# v2.net
KiCad netlist of a schematic drawn in EAGLE
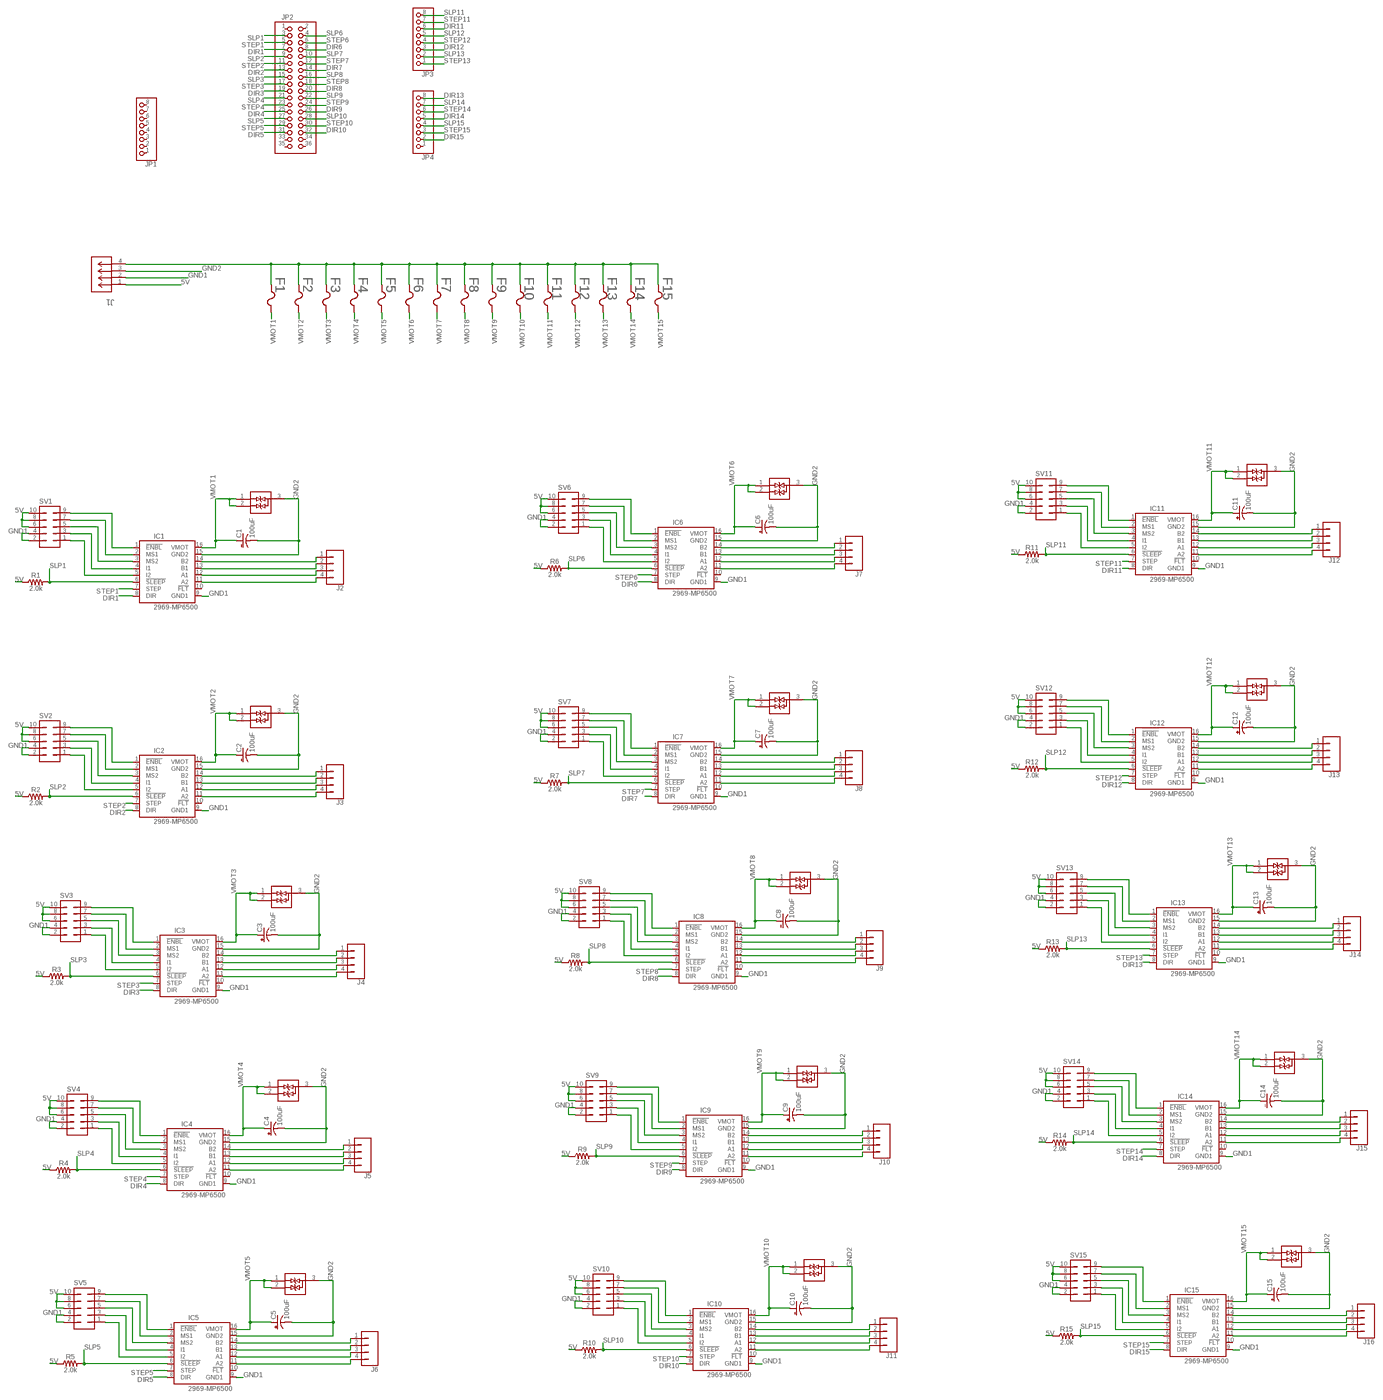
[diagram p0: schematic, sheet 1, overview]
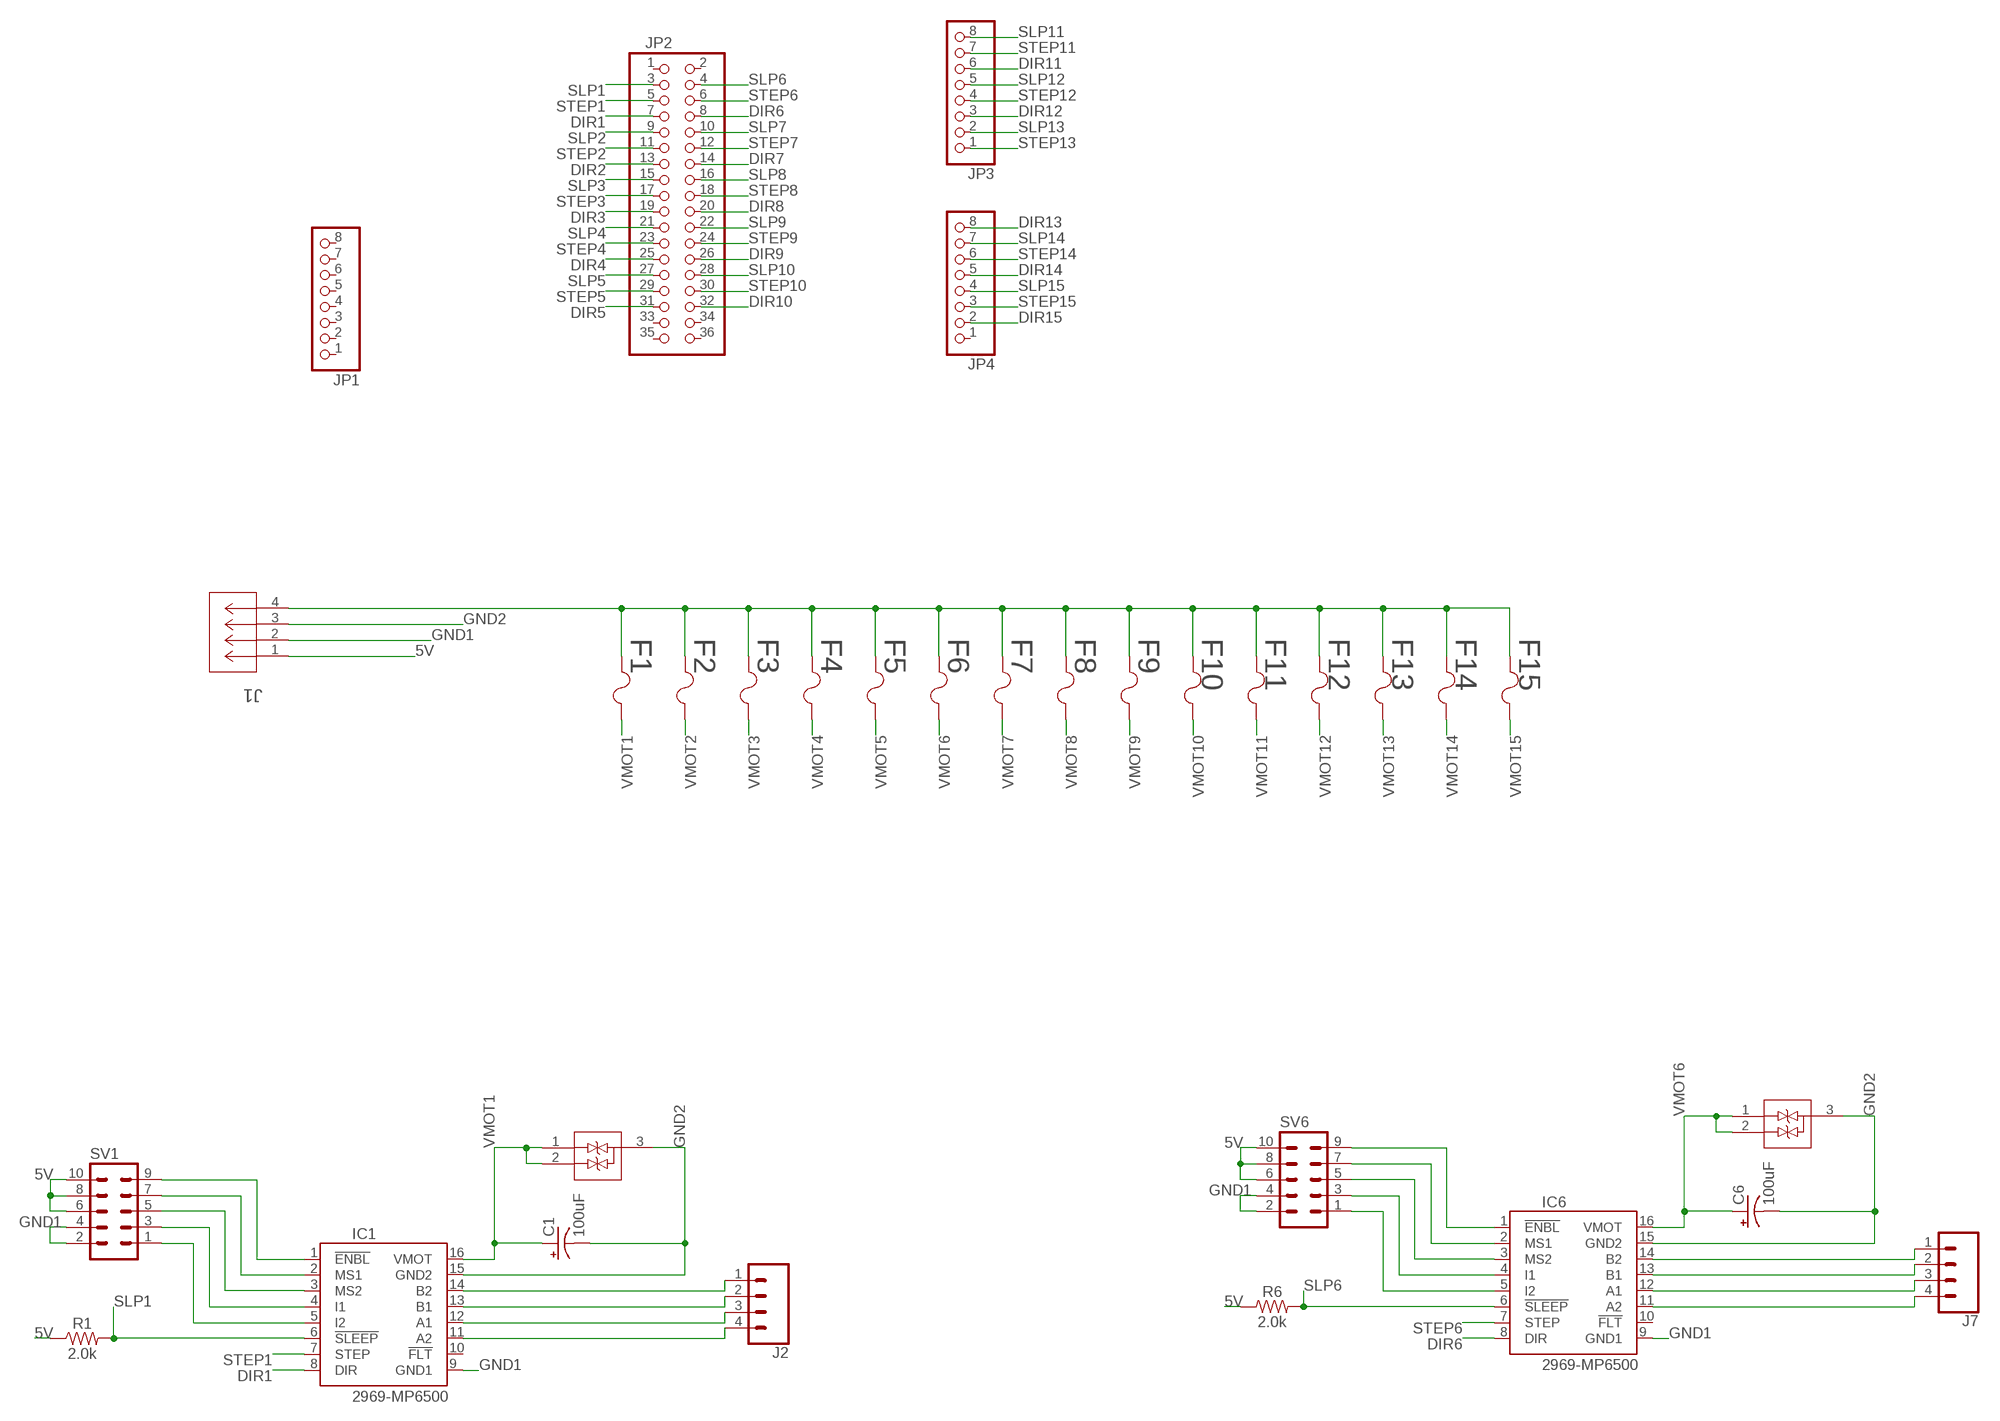
[diagram p1: schematic, sheet 1, part 1 of 4]
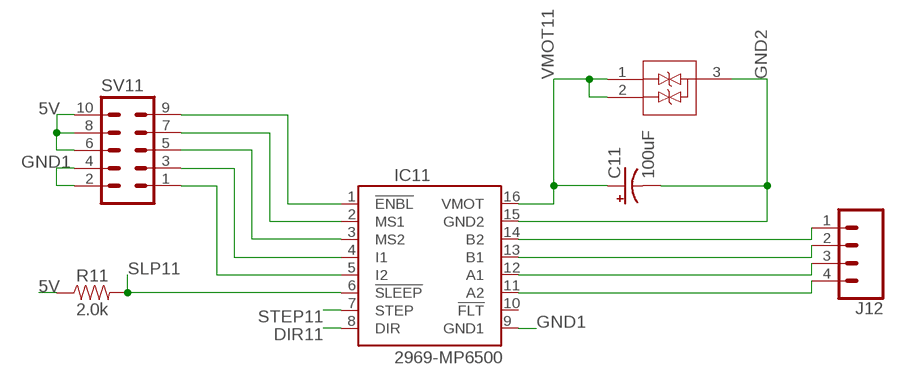
[diagram p2: schematic, sheet 1, part 2 of 4]
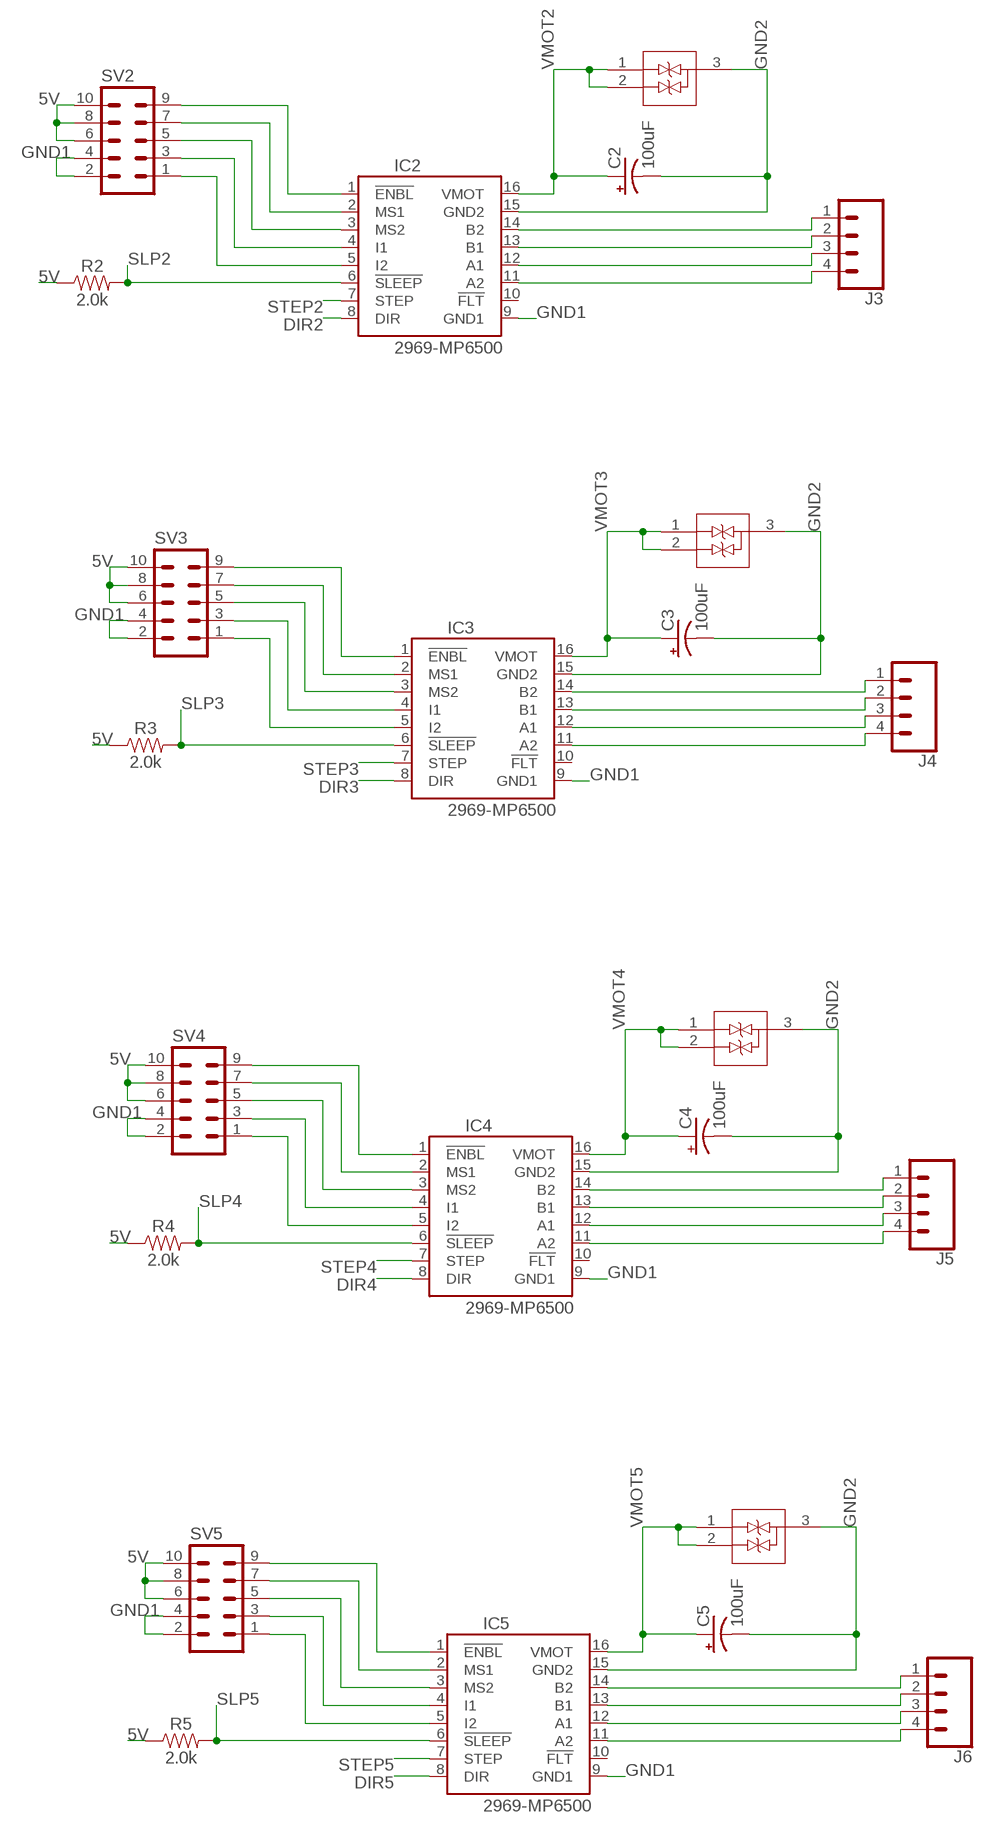
[diagram p3: schematic, sheet 1, part 3 of 4]
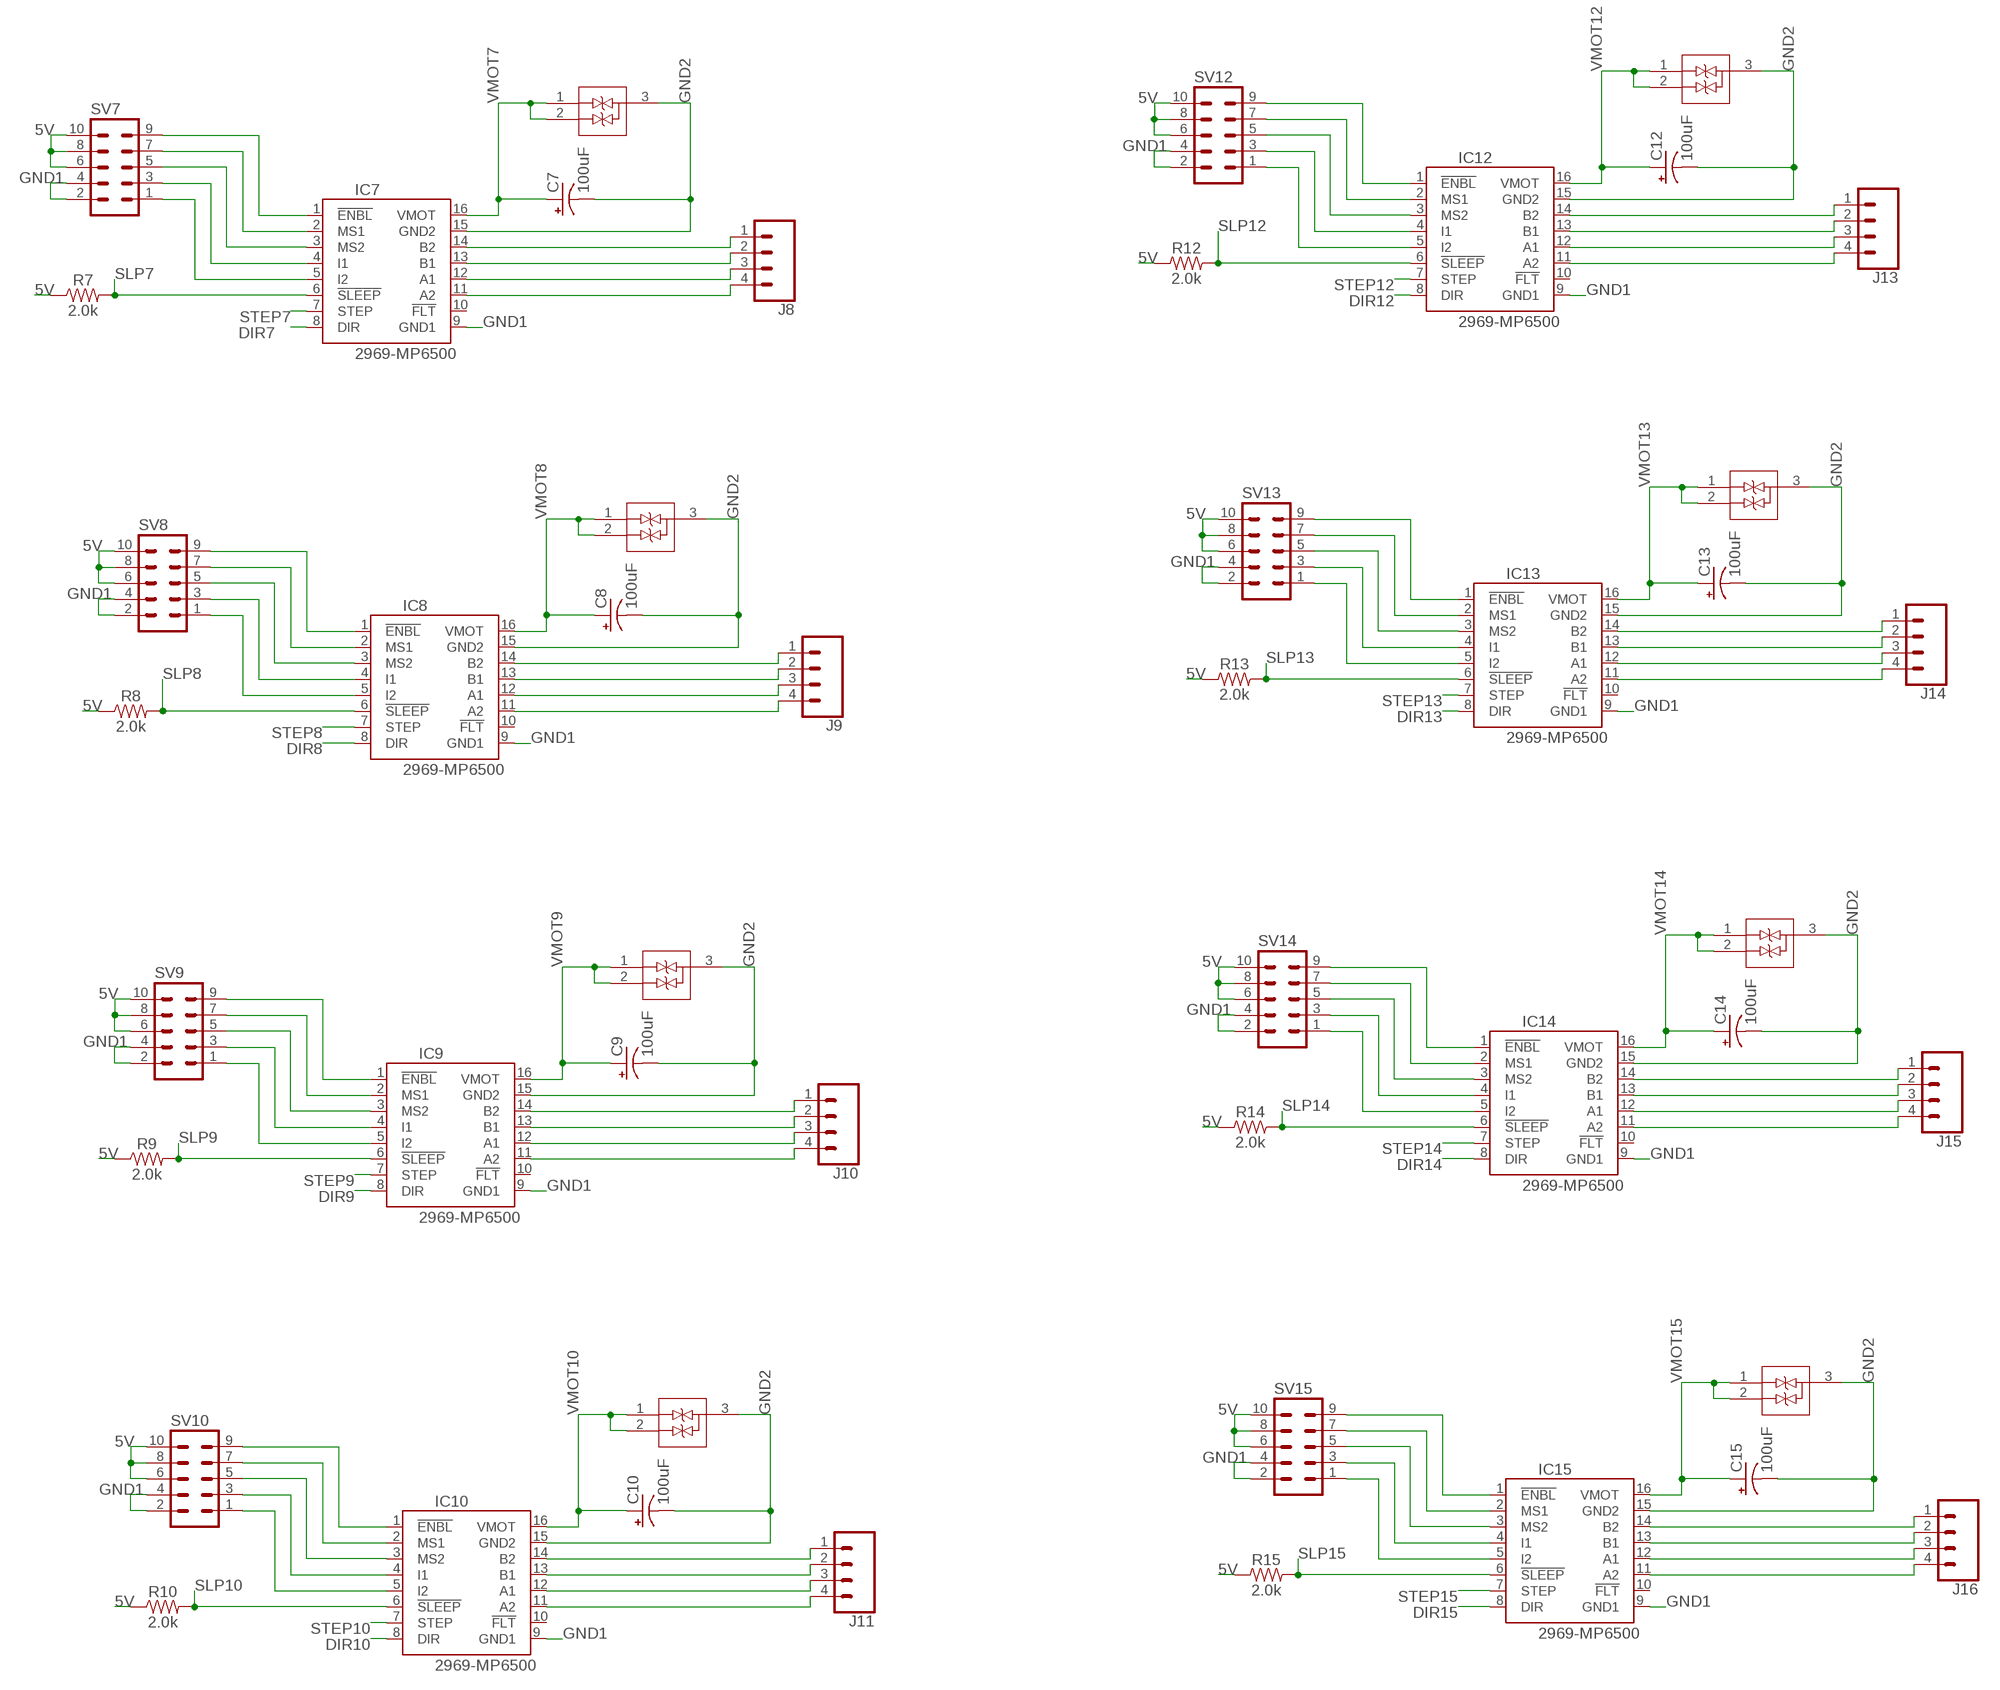
[diagram p4: schematic, sheet 1, part 4 of 4]

(export (version "E")
  (design (tool "Eeschema 10.0.6"))
  (components
    (comp (ref "C1")
      (value "100uF")
      (footprint "eagle-import:8X10.5")
      (libsource (lib "eagle-import") (part "100UF-POLAR-8X10.5-50V"))
    )
    (comp (ref "C2")
      (value "100uF")
      (footprint "eagle-import:8X10.5")
      (libsource (lib "eagle-import") (part "100UF-POLAR-8X10.5-50V"))
    )
    (comp (ref "C3")
      (value "100uF")
      (footprint "eagle-import:8X10.5")
      (libsource (lib "eagle-import") (part "100UF-POLAR-8X10.5-50V"))
    )
    (comp (ref "C4")
      (value "100uF")
      (footprint "eagle-import:8X10.5")
      (libsource (lib "eagle-import") (part "100UF-POLAR-8X10.5-50V"))
    )
    (comp (ref "C5")
      (value "100uF")
      (footprint "eagle-import:8X10.5")
      (libsource (lib "eagle-import") (part "100UF-POLAR-8X10.5-50V"))
    )
    (comp (ref "C6")
      (value "100uF")
      (footprint "eagle-import:8X10.5")
      (libsource (lib "eagle-import") (part "100UF-POLAR-8X10.5-50V"))
    )
    (comp (ref "C7")
      (value "100uF")
      (footprint "eagle-import:8X10.5")
      (libsource (lib "eagle-import") (part "100UF-POLAR-8X10.5-50V"))
    )
    (comp (ref "C8")
      (value "100uF")
      (footprint "eagle-import:8X10.5")
      (libsource (lib "eagle-import") (part "100UF-POLAR-8X10.5-50V"))
    )
    (comp (ref "C9")
      (value "100uF")
      (footprint "eagle-import:8X10.5")
      (libsource (lib "eagle-import") (part "100UF-POLAR-8X10.5-50V"))
    )
    (comp (ref "C10")
      (value "100uF")
      (footprint "eagle-import:8X10.5")
      (libsource (lib "eagle-import") (part "100UF-POLAR-8X10.5-50V"))
    )
    (comp (ref "C11")
      (value "100uF")
      (footprint "eagle-import:8X10.5")
      (libsource (lib "eagle-import") (part "100UF-POLAR-8X10.5-50V"))
    )
    (comp (ref "C12")
      (value "100uF")
      (footprint "eagle-import:8X10.5")
      (libsource (lib "eagle-import") (part "100UF-POLAR-8X10.5-50V"))
    )
    (comp (ref "C13")
      (value "100uF")
      (footprint "eagle-import:8X10.5")
      (libsource (lib "eagle-import") (part "100UF-POLAR-8X10.5-50V"))
    )
    (comp (ref "C14")
      (value "100uF")
      (footprint "eagle-import:8X10.5")
      (libsource (lib "eagle-import") (part "100UF-POLAR-8X10.5-50V"))
    )
    (comp (ref "C15")
      (value "100uF")
      (footprint "eagle-import:8X10.5")
      (libsource (lib "eagle-import") (part "100UF-POLAR-8X10.5-50V"))
    )
    (comp (ref "CR1")
      (value "PESD2CAN24DBZRQ1")
      (footprint "eagle-import:SOT-23_DBZ_TEX")
      (fields (field (name "COPYRIGHT") "Copyright (C) 2023 Ultra Librarian. All rights reserved."))
      (libsource (lib "eagle-import") (part "PESD2CAN24DBZRQ1"))
    )
    (comp (ref "CR2")
      (value "PESD2CAN24DBZRQ1")
      (footprint "eagle-import:SOT-23_DBZ_TEX")
      (fields (field (name "COPYRIGHT") "Copyright (C) 2023 Ultra Librarian. All rights reserved."))
      (libsource (lib "eagle-import") (part "PESD2CAN24DBZRQ1"))
    )
    (comp (ref "CR3")
      (value "PESD2CAN24DBZRQ1")
      (footprint "eagle-import:SOT-23_DBZ_TEX")
      (fields (field (name "COPYRIGHT") "Copyright (C) 2023 Ultra Librarian. All rights reserved."))
      (libsource (lib "eagle-import") (part "PESD2CAN24DBZRQ1"))
    )
    (comp (ref "CR4")
      (value "PESD2CAN24DBZRQ1")
      (footprint "eagle-import:SOT-23_DBZ_TEX")
      (fields (field (name "COPYRIGHT") "Copyright (C) 2023 Ultra Librarian. All rights reserved."))
      (libsource (lib "eagle-import") (part "PESD2CAN24DBZRQ1"))
    )
    (comp (ref "CR5")
      (value "PESD2CAN24DBZRQ1")
      (footprint "eagle-import:SOT-23_DBZ_TEX")
      (fields (field (name "COPYRIGHT") "Copyright (C) 2023 Ultra Librarian. All rights reserved."))
      (libsource (lib "eagle-import") (part "PESD2CAN24DBZRQ1"))
    )
    (comp (ref "CR6")
      (value "PESD2CAN24DBZRQ1")
      (footprint "eagle-import:SOT-23_DBZ_TEX")
      (fields (field (name "COPYRIGHT") "Copyright (C) 2023 Ultra Librarian. All rights reserved."))
      (libsource (lib "eagle-import") (part "PESD2CAN24DBZRQ1"))
    )
    (comp (ref "CR7")
      (value "PESD2CAN24DBZRQ1")
      (footprint "eagle-import:SOT-23_DBZ_TEX")
      (fields (field (name "COPYRIGHT") "Copyright (C) 2023 Ultra Librarian. All rights reserved."))
      (libsource (lib "eagle-import") (part "PESD2CAN24DBZRQ1"))
    )
    (comp (ref "CR8")
      (value "PESD2CAN24DBZRQ1")
      (footprint "eagle-import:SOT-23_DBZ_TEX")
      (fields (field (name "COPYRIGHT") "Copyright (C) 2023 Ultra Librarian. All rights reserved."))
      (libsource (lib "eagle-import") (part "PESD2CAN24DBZRQ1"))
    )
    (comp (ref "CR9")
      (value "PESD2CAN24DBZRQ1")
      (footprint "eagle-import:SOT-23_DBZ_TEX")
      (fields (field (name "COPYRIGHT") "Copyright (C) 2023 Ultra Librarian. All rights reserved."))
      (libsource (lib "eagle-import") (part "PESD2CAN24DBZRQ1"))
    )
    (comp (ref "CR10")
      (value "PESD2CAN24DBZRQ1")
      (footprint "eagle-import:SOT-23_DBZ_TEX")
      (fields (field (name "COPYRIGHT") "Copyright (C) 2023 Ultra Librarian. All rights reserved."))
      (libsource (lib "eagle-import") (part "PESD2CAN24DBZRQ1"))
    )
    (comp (ref "CR11")
      (value "PESD2CAN24DBZRQ1")
      (footprint "eagle-import:SOT-23_DBZ_TEX")
      (fields (field (name "COPYRIGHT") "Copyright (C) 2023 Ultra Librarian. All rights reserved."))
      (libsource (lib "eagle-import") (part "PESD2CAN24DBZRQ1"))
    )
    (comp (ref "CR12")
      (value "PESD2CAN24DBZRQ1")
      (footprint "eagle-import:SOT-23_DBZ_TEX")
      (fields (field (name "COPYRIGHT") "Copyright (C) 2023 Ultra Librarian. All rights reserved."))
      (libsource (lib "eagle-import") (part "PESD2CAN24DBZRQ1"))
    )
    (comp (ref "CR13")
      (value "PESD2CAN24DBZRQ1")
      (footprint "eagle-import:SOT-23_DBZ_TEX")
      (fields (field (name "COPYRIGHT") "Copyright (C) 2023 Ultra Librarian. All rights reserved."))
      (libsource (lib "eagle-import") (part "PESD2CAN24DBZRQ1"))
    )
    (comp (ref "CR14")
      (value "PESD2CAN24DBZRQ1")
      (footprint "eagle-import:SOT-23_DBZ_TEX")
      (fields (field (name "COPYRIGHT") "Copyright (C) 2023 Ultra Librarian. All rights reserved."))
      (libsource (lib "eagle-import") (part "PESD2CAN24DBZRQ1"))
    )
    (comp (ref "CR15")
      (value "PESD2CAN24DBZRQ1")
      (footprint "eagle-import:SOT-23_DBZ_TEX")
      (fields (field (name "COPYRIGHT") "Copyright (C) 2023 Ultra Librarian. All rights reserved."))
      (libsource (lib "eagle-import") (part "PESD2CAN24DBZRQ1"))
    )
    (comp (ref "F1")
      (value "0154003.DR")
      (footprint "eagle-import:0154SERIES_LTF")
      (fields (field (name "COPYRIGHT") "Copyright (C) 2023 Ultra Librarian. All rights reserved."))
      (libsource (lib "eagle-import") (part "0154003.DR"))
    )
    (comp (ref "F2")
      (value "0154003.DR")
      (footprint "eagle-import:0154SERIES_LTF")
      (fields (field (name "COPYRIGHT") "Copyright (C) 2023 Ultra Librarian. All rights reserved."))
      (libsource (lib "eagle-import") (part "0154003.DR"))
    )
    (comp (ref "F3")
      (value "0154003.DR")
      (footprint "eagle-import:0154SERIES_LTF")
      (fields (field (name "COPYRIGHT") "Copyright (C) 2023 Ultra Librarian. All rights reserved."))
      (libsource (lib "eagle-import") (part "0154003.DR"))
    )
    (comp (ref "F4")
      (value "0154003.DR")
      (footprint "eagle-import:0154SERIES_LTF")
      (fields (field (name "COPYRIGHT") "Copyright (C) 2023 Ultra Librarian. All rights reserved."))
      (libsource (lib "eagle-import") (part "0154003.DR"))
    )
    (comp (ref "F5")
      (value "0154003.DR")
      (footprint "eagle-import:0154SERIES_LTF")
      (fields (field (name "COPYRIGHT") "Copyright (C) 2023 Ultra Librarian. All rights reserved."))
      (libsource (lib "eagle-import") (part "0154003.DR"))
    )
    (comp (ref "F6")
      (value "0154003.DR")
      (footprint "eagle-import:0154SERIES_LTF")
      (fields (field (name "COPYRIGHT") "Copyright (C) 2023 Ultra Librarian. All rights reserved."))
      (libsource (lib "eagle-import") (part "0154003.DR"))
    )
    (comp (ref "F7")
      (value "0154003.DR")
      (footprint "eagle-import:0154SERIES_LTF")
      (fields (field (name "COPYRIGHT") "Copyright (C) 2023 Ultra Librarian. All rights reserved."))
      (libsource (lib "eagle-import") (part "0154003.DR"))
    )
    (comp (ref "F8")
      (value "0154003.DR")
      (footprint "eagle-import:0154SERIES_LTF")
      (fields (field (name "COPYRIGHT") "Copyright (C) 2023 Ultra Librarian. All rights reserved."))
      (libsource (lib "eagle-import") (part "0154003.DR"))
    )
    (comp (ref "F9")
      (value "0154003.DR")
      (footprint "eagle-import:0154SERIES_LTF")
      (fields (field (name "COPYRIGHT") "Copyright (C) 2023 Ultra Librarian. All rights reserved."))
      (libsource (lib "eagle-import") (part "0154003.DR"))
    )
    (comp (ref "F10")
      (value "0154003.DR")
      (footprint "eagle-import:0154SERIES_LTF")
      (fields (field (name "COPYRIGHT") "Copyright (C) 2023 Ultra Librarian. All rights reserved."))
      (libsource (lib "eagle-import") (part "0154003.DR"))
    )
    (comp (ref "F11")
      (value "0154003.DR")
      (footprint "eagle-import:0154SERIES_LTF")
      (fields (field (name "COPYRIGHT") "Copyright (C) 2023 Ultra Librarian. All rights reserved."))
      (libsource (lib "eagle-import") (part "0154003.DR"))
    )
    (comp (ref "F12")
      (value "0154003.DR")
      (footprint "eagle-import:0154SERIES_LTF")
      (fields (field (name "COPYRIGHT") "Copyright (C) 2023 Ultra Librarian. All rights reserved."))
      (libsource (lib "eagle-import") (part "0154003.DR"))
    )
    (comp (ref "F13")
      (value "0154003.DR")
      (footprint "eagle-import:0154SERIES_LTF")
      (fields (field (name "COPYRIGHT") "Copyright (C) 2023 Ultra Librarian. All rights reserved."))
      (libsource (lib "eagle-import") (part "0154003.DR"))
    )
    (comp (ref "F14")
      (value "0154003.DR")
      (footprint "eagle-import:0154SERIES_LTF")
      (fields (field (name "COPYRIGHT") "Copyright (C) 2023 Ultra Librarian. All rights reserved."))
      (libsource (lib "eagle-import") (part "0154003.DR"))
    )
    (comp (ref "F15")
      (value "0154003.DR")
      (footprint "eagle-import:0154SERIES_LTF")
      (fields (field (name "COPYRIGHT") "Copyright (C) 2023 Ultra Librarian. All rights reserved."))
      (libsource (lib "eagle-import") (part "0154003.DR"))
    )
    (comp (ref "IC1")
      (value "2969-MP6500")
      (footprint "eagle-import:MP6500")
      (libsource (lib "eagle-import") (part "2969-MP6500"))
    )
    (comp (ref "IC2")
      (value "2969-MP6500")
      (footprint "eagle-import:MP6500")
      (libsource (lib "eagle-import") (part "2969-MP6500"))
    )
    (comp (ref "IC3")
      (value "2969-MP6500")
      (footprint "eagle-import:MP6500")
      (libsource (lib "eagle-import") (part "2969-MP6500"))
    )
    (comp (ref "IC4")
      (value "2969-MP6500")
      (footprint "eagle-import:MP6500")
      (libsource (lib "eagle-import") (part "2969-MP6500"))
    )
    (comp (ref "IC5")
      (value "2969-MP6500")
      (footprint "eagle-import:MP6500")
      (libsource (lib "eagle-import") (part "2969-MP6500"))
    )
    (comp (ref "IC6")
      (value "2969-MP6500")
      (footprint "eagle-import:MP6500")
      (libsource (lib "eagle-import") (part "2969-MP6500"))
    )
    (comp (ref "IC7")
      (value "2969-MP6500")
      (footprint "eagle-import:MP6500")
      (libsource (lib "eagle-import") (part "2969-MP6500"))
    )
    (comp (ref "IC8")
      (value "2969-MP6500")
      (footprint "eagle-import:MP6500")
      (libsource (lib "eagle-import") (part "2969-MP6500"))
    )
    (comp (ref "IC9")
      (value "2969-MP6500")
      (footprint "eagle-import:MP6500")
      (libsource (lib "eagle-import") (part "2969-MP6500"))
    )
    (comp (ref "IC10")
      (value "2969-MP6500")
      (footprint "eagle-import:MP6500")
      (libsource (lib "eagle-import") (part "2969-MP6500"))
    )
    (comp (ref "IC11")
      (value "2969-MP6500")
      (footprint "eagle-import:MP6500")
      (libsource (lib "eagle-import") (part "2969-MP6500"))
    )
    (comp (ref "IC12")
      (value "2969-MP6500")
      (footprint "eagle-import:MP6500")
      (libsource (lib "eagle-import") (part "2969-MP6500"))
    )
    (comp (ref "IC13")
      (value "2969-MP6500")
      (footprint "eagle-import:MP6500")
      (libsource (lib "eagle-import") (part "2969-MP6500"))
    )
    (comp (ref "IC14")
      (value "2969-MP6500")
      (footprint "eagle-import:MP6500")
      (libsource (lib "eagle-import") (part "2969-MP6500"))
    )
    (comp (ref "IC15")
      (value "2969-MP6500")
      (footprint "eagle-import:MP6500")
      (libsource (lib "eagle-import") (part "2969-MP6500"))
    )
    (comp (ref "J1")
      (value "1888700")
      (footprint "eagle-import:CONN_1888700_PXC")
      (fields (field (name "COPYRIGHT") "Copyright (C) 2023 Ultra Librarian. All rights reserved."))
      (libsource (lib "eagle-import") (part "1888700"))
    )
    (comp (ref "J2")
      (value "CONN_04POLAR_LOCK")
      (footprint "eagle-import:MOLEX-1X4_LOCK")
      (libsource (lib "eagle-import") (part "CONN_04POLAR_LOCK"))
    )
    (comp (ref "J3")
      (value "CONN_04POLAR_LOCK")
      (footprint "eagle-import:MOLEX-1X4_LOCK")
      (libsource (lib "eagle-import") (part "CONN_04POLAR_LOCK"))
    )
    (comp (ref "J4")
      (value "CONN_04POLAR_LOCK")
      (footprint "eagle-import:MOLEX-1X4_LOCK")
      (libsource (lib "eagle-import") (part "CONN_04POLAR_LOCK"))
    )
    (comp (ref "J5")
      (value "CONN_04POLAR_LOCK")
      (footprint "eagle-import:MOLEX-1X4_LOCK")
      (libsource (lib "eagle-import") (part "CONN_04POLAR_LOCK"))
    )
    (comp (ref "J6")
      (value "CONN_04POLAR_LOCK")
      (footprint "eagle-import:MOLEX-1X4_LOCK")
      (libsource (lib "eagle-import") (part "CONN_04POLAR_LOCK"))
    )
    (comp (ref "J7")
      (value "CONN_04POLAR_LOCK")
      (footprint "eagle-import:MOLEX-1X4_LOCK")
      (libsource (lib "eagle-import") (part "CONN_04POLAR_LOCK"))
    )
    (comp (ref "J8")
      (value "CONN_04POLAR_LOCK")
      (footprint "eagle-import:MOLEX-1X4_LOCK")
      (libsource (lib "eagle-import") (part "CONN_04POLAR_LOCK"))
    )
    (comp (ref "J9")
      (value "CONN_04POLAR_LOCK")
      (footprint "eagle-import:MOLEX-1X4_LOCK")
      (libsource (lib "eagle-import") (part "CONN_04POLAR_LOCK"))
    )
    (comp (ref "J10")
      (value "CONN_04POLAR_LOCK")
      (footprint "eagle-import:MOLEX-1X4_LOCK")
      (libsource (lib "eagle-import") (part "CONN_04POLAR_LOCK"))
    )
    (comp (ref "J11")
      (value "CONN_04POLAR_LOCK")
      (footprint "eagle-import:MOLEX-1X4_LOCK")
      (libsource (lib "eagle-import") (part "CONN_04POLAR_LOCK"))
    )
    (comp (ref "J12")
      (value "CONN_04POLAR_LOCK")
      (footprint "eagle-import:MOLEX-1X4_LOCK")
      (libsource (lib "eagle-import") (part "CONN_04POLAR_LOCK"))
    )
    (comp (ref "J13")
      (value "CONN_04POLAR_LOCK")
      (footprint "eagle-import:MOLEX-1X4_LOCK")
      (libsource (lib "eagle-import") (part "CONN_04POLAR_LOCK"))
    )
    (comp (ref "J14")
      (value "CONN_04POLAR_LOCK")
      (footprint "eagle-import:MOLEX-1X4_LOCK")
      (libsource (lib "eagle-import") (part "CONN_04POLAR_LOCK"))
    )
    (comp (ref "J15")
      (value "CONN_04POLAR_LOCK")
      (footprint "eagle-import:MOLEX-1X4_LOCK")
      (libsource (lib "eagle-import") (part "CONN_04POLAR_LOCK"))
    )
    (comp (ref "J16")
      (value "CONN_04POLAR_LOCK")
      (footprint "eagle-import:MOLEX-1X4_LOCK")
      (libsource (lib "eagle-import") (part "CONN_04POLAR_LOCK"))
    )
    (comp (ref "JP1")
      (value "PINHD-1X8")
      (footprint "eagle-import:1X08")
      (libsource (lib "eagle-import") (part "PINHD-1X8"))
    )
    (comp (ref "JP2")
      (value "PINHD-2X18")
      (footprint "eagle-import:2X18")
      (libsource (lib "eagle-import") (part "PINHD-2X18"))
    )
    (comp (ref "JP3")
      (value "PINHD-1X8")
      (footprint "eagle-import:1X08")
      (libsource (lib "eagle-import") (part "PINHD-1X8"))
    )
    (comp (ref "JP4")
      (value "PINHD-1X8")
      (footprint "eagle-import:1X08")
      (libsource (lib "eagle-import") (part "PINHD-1X8"))
    )
    (comp (ref "R1")
      (value "2.0k")
      (footprint "eagle-import:0603")
      (libsource (lib "eagle-import") (part "2.0KOHM-0603-1/10W-5%"))
    )
    (comp (ref "R2")
      (value "2.0k")
      (footprint "eagle-import:0603")
      (libsource (lib "eagle-import") (part "2.0KOHM-0603-1/10W-5%"))
    )
    (comp (ref "R3")
      (value "2.0k")
      (footprint "eagle-import:0603")
      (libsource (lib "eagle-import") (part "2.0KOHM-0603-1/10W-5%"))
    )
    (comp (ref "R4")
      (value "2.0k")
      (footprint "eagle-import:0603")
      (libsource (lib "eagle-import") (part "2.0KOHM-0603-1/10W-5%"))
    )
    (comp (ref "R5")
      (value "2.0k")
      (footprint "eagle-import:0603")
      (libsource (lib "eagle-import") (part "2.0KOHM-0603-1/10W-5%"))
    )
    (comp (ref "R6")
      (value "2.0k")
      (footprint "eagle-import:0603")
      (libsource (lib "eagle-import") (part "2.0KOHM-0603-1/10W-5%"))
    )
    (comp (ref "R7")
      (value "2.0k")
      (footprint "eagle-import:0603")
      (libsource (lib "eagle-import") (part "2.0KOHM-0603-1/10W-5%"))
    )
    (comp (ref "R8")
      (value "2.0k")
      (footprint "eagle-import:0603")
      (libsource (lib "eagle-import") (part "2.0KOHM-0603-1/10W-5%"))
    )
    (comp (ref "R9")
      (value "2.0k")
      (footprint "eagle-import:0603")
      (libsource (lib "eagle-import") (part "2.0KOHM-0603-1/10W-5%"))
    )
    (comp (ref "R10")
      (value "2.0k")
      (footprint "eagle-import:0603")
      (libsource (lib "eagle-import") (part "2.0KOHM-0603-1/10W-5%"))
    )
    (comp (ref "R11")
      (value "2.0k")
      (footprint "eagle-import:0603")
      (libsource (lib "eagle-import") (part "2.0KOHM-0603-1/10W-5%"))
    )
    (comp (ref "R12")
      (value "2.0k")
      (footprint "eagle-import:0603")
      (libsource (lib "eagle-import") (part "2.0KOHM-0603-1/10W-5%"))
    )
    (comp (ref "R13")
      (value "2.0k")
      (footprint "eagle-import:0603")
      (libsource (lib "eagle-import") (part "2.0KOHM-0603-1/10W-5%"))
    )
    (comp (ref "R14")
      (value "2.0k")
      (footprint "eagle-import:0603")
      (libsource (lib "eagle-import") (part "2.0KOHM-0603-1/10W-5%"))
    )
    (comp (ref "R15")
      (value "2.0k")
      (footprint "eagle-import:0603")
      (libsource (lib "eagle-import") (part "2.0KOHM-0603-1/10W-5%"))
    )
    (comp (ref "SV1")
      (value "MA05-2")
      (footprint "eagle-import:MA05-2")
      (libsource (lib "eagle-import") (part "MA05-2"))
    )
    (comp (ref "SV2")
      (value "MA05-2")
      (footprint "eagle-import:MA05-2")
      (libsource (lib "eagle-import") (part "MA05-2"))
    )
    (comp (ref "SV3")
      (value "MA05-2")
      (footprint "eagle-import:MA05-2")
      (libsource (lib "eagle-import") (part "MA05-2"))
    )
    (comp (ref "SV4")
      (value "MA05-2")
      (footprint "eagle-import:MA05-2")
      (libsource (lib "eagle-import") (part "MA05-2"))
    )
    (comp (ref "SV5")
      (value "MA05-2")
      (footprint "eagle-import:MA05-2")
      (libsource (lib "eagle-import") (part "MA05-2"))
    )
    (comp (ref "SV6")
      (value "MA05-2")
      (footprint "eagle-import:MA05-2")
      (libsource (lib "eagle-import") (part "MA05-2"))
    )
    (comp (ref "SV7")
      (value "MA05-2")
      (footprint "eagle-import:MA05-2")
      (libsource (lib "eagle-import") (part "MA05-2"))
    )
    (comp (ref "SV8")
      (value "MA05-2")
      (footprint "eagle-import:MA05-2")
      (libsource (lib "eagle-import") (part "MA05-2"))
    )
    (comp (ref "SV9")
      (value "MA05-2")
      (footprint "eagle-import:MA05-2")
      (libsource (lib "eagle-import") (part "MA05-2"))
    )
    (comp (ref "SV10")
      (value "MA05-2")
      (footprint "eagle-import:MA05-2")
      (libsource (lib "eagle-import") (part "MA05-2"))
    )
    (comp (ref "SV11")
      (value "MA05-2")
      (footprint "eagle-import:MA05-2")
      (libsource (lib "eagle-import") (part "MA05-2"))
    )
    (comp (ref "SV12")
      (value "MA05-2")
      (footprint "eagle-import:MA05-2")
      (libsource (lib "eagle-import") (part "MA05-2"))
    )
    (comp (ref "SV13")
      (value "MA05-2")
      (footprint "eagle-import:MA05-2")
      (libsource (lib "eagle-import") (part "MA05-2"))
    )
    (comp (ref "SV14")
      (value "MA05-2")
      (footprint "eagle-import:MA05-2")
      (libsource (lib "eagle-import") (part "MA05-2"))
    )
    (comp (ref "SV15")
      (value "MA05-2")
      (footprint "eagle-import:MA05-2")
      (libsource (lib "eagle-import") (part "MA05-2"))
    )
  )
  (nets
    (net (code "1") (name "/5V") (class "Default")
      (node (ref "J1") (pin "1") (pinfunction "1_1") (pintype "passive"))
      (node (ref "R1") (pin "1") (pinfunction "1_1") (pintype "passive"))
      (node (ref "R10") (pin "1") (pinfunction "1_1") (pintype "passive"))
      (node (ref "R11") (pin "1") (pinfunction "1_1") (pintype "passive"))
      (node (ref "R12") (pin "1") (pinfunction "1_1") (pintype "passive"))
      (node (ref "R13") (pin "1") (pinfunction "1_1") (pintype "passive"))
      (node (ref "R14") (pin "1") (pinfunction "1_1") (pintype "passive"))
      (node (ref "R15") (pin "1") (pinfunction "1_1") (pintype "passive"))
      (node (ref "R2") (pin "1") (pinfunction "1_1") (pintype "passive"))
      (node (ref "R3") (pin "1") (pinfunction "1_1") (pintype "passive"))
      (node (ref "R4") (pin "1") (pinfunction "1_1") (pintype "passive"))
      (node (ref "R5") (pin "1") (pinfunction "1_1") (pintype "passive"))
      (node (ref "R6") (pin "1") (pinfunction "1_1") (pintype "passive"))
      (node (ref "R7") (pin "1") (pinfunction "1_1") (pintype "passive"))
      (node (ref "R8") (pin "1") (pinfunction "1_1") (pintype "passive"))
      (node (ref "R9") (pin "1") (pinfunction "1_1") (pintype "passive"))
      (node (ref "SV1") (pin "10") (pinfunction "10_10") (pintype "passive"))
      (node (ref "SV1") (pin "6") (pinfunction "6_6") (pintype "passive"))
      (node (ref "SV1") (pin "8") (pinfunction "8_8") (pintype "passive"))
      (node (ref "SV10") (pin "10") (pinfunction "10_10") (pintype "passive"))
      (node (ref "SV10") (pin "6") (pinfunction "6_6") (pintype "passive"))
      (node (ref "SV10") (pin "8") (pinfunction "8_8") (pintype "passive"))
      (node (ref "SV11") (pin "10") (pinfunction "10_10") (pintype "passive"))
      (node (ref "SV11") (pin "6") (pinfunction "6_6") (pintype "passive"))
      (node (ref "SV11") (pin "8") (pinfunction "8_8") (pintype "passive"))
      (node (ref "SV12") (pin "10") (pinfunction "10_10") (pintype "passive"))
      (node (ref "SV12") (pin "6") (pinfunction "6_6") (pintype "passive"))
      (node (ref "SV12") (pin "8") (pinfunction "8_8") (pintype "passive"))
      (node (ref "SV13") (pin "10") (pinfunction "10_10") (pintype "passive"))
      (node (ref "SV13") (pin "6") (pinfunction "6_6") (pintype "passive"))
      (node (ref "SV13") (pin "8") (pinfunction "8_8") (pintype "passive"))
      (node (ref "SV14") (pin "10") (pinfunction "10_10") (pintype "passive"))
      (node (ref "SV14") (pin "6") (pinfunction "6_6") (pintype "passive"))
      (node (ref "SV14") (pin "8") (pinfunction "8_8") (pintype "passive"))
      (node (ref "SV15") (pin "10") (pinfunction "10_10") (pintype "passive"))
      (node (ref "SV15") (pin "6") (pinfunction "6_6") (pintype "passive"))
      (node (ref "SV15") (pin "8") (pinfunction "8_8") (pintype "passive"))
      (node (ref "SV2") (pin "10") (pinfunction "10_10") (pintype "passive"))
      (node (ref "SV2") (pin "6") (pinfunction "6_6") (pintype "passive"))
      (node (ref "SV2") (pin "8") (pinfunction "8_8") (pintype "passive"))
      (node (ref "SV3") (pin "10") (pinfunction "10_10") (pintype "passive"))
      (node (ref "SV3") (pin "6") (pinfunction "6_6") (pintype "passive"))
      (node (ref "SV3") (pin "8") (pinfunction "8_8") (pintype "passive"))
      (node (ref "SV4") (pin "10") (pinfunction "10_10") (pintype "passive"))
      (node (ref "SV4") (pin "6") (pinfunction "6_6") (pintype "passive"))
      (node (ref "SV4") (pin "8") (pinfunction "8_8") (pintype "passive"))
      (node (ref "SV5") (pin "10") (pinfunction "10_10") (pintype "passive"))
      (node (ref "SV5") (pin "6") (pinfunction "6_6") (pintype "passive"))
      (node (ref "SV5") (pin "8") (pinfunction "8_8") (pintype "passive"))
      (node (ref "SV6") (pin "10") (pinfunction "10_10") (pintype "passive"))
      (node (ref "SV6") (pin "6") (pinfunction "6_6") (pintype "passive"))
      (node (ref "SV6") (pin "8") (pinfunction "8_8") (pintype "passive"))
      (node (ref "SV7") (pin "10") (pinfunction "10_10") (pintype "passive"))
      (node (ref "SV7") (pin "6") (pinfunction "6_6") (pintype "passive"))
      (node (ref "SV7") (pin "8") (pinfunction "8_8") (pintype "passive"))
      (node (ref "SV8") (pin "10") (pinfunction "10_10") (pintype "passive"))
      (node (ref "SV8") (pin "6") (pinfunction "6_6") (pintype "passive"))
      (node (ref "SV8") (pin "8") (pinfunction "8_8") (pintype "passive"))
      (node (ref "SV9") (pin "10") (pinfunction "10_10") (pintype "passive"))
      (node (ref "SV9") (pin "6") (pinfunction "6_6") (pintype "passive"))
      (node (ref "SV9") (pin "8") (pinfunction "8_8") (pintype "passive"))
    )
    (net (code "2") (name "/DIR1") (class "Default")
      (node (ref "IC1") (pin "8") (pinfunction "DIR_8") (pintype "input"))
      (node (ref "JP2") (pin "7") (pinfunction "7_7") (pintype "passive"))
    )
    (net (code "3") (name "/DIR2") (class "Default")
      (node (ref "IC2") (pin "8") (pinfunction "DIR_8") (pintype "input"))
      (node (ref "JP2") (pin "13") (pinfunction "13_13") (pintype "passive"))
    )
    (net (code "4") (name "/DIR3") (class "Default")
      (node (ref "IC3") (pin "8") (pinfunction "DIR_8") (pintype "input"))
      (node (ref "JP2") (pin "19") (pinfunction "19_19") (pintype "passive"))
    )
    (net (code "5") (name "/DIR4") (class "Default")
      (node (ref "IC4") (pin "8") (pinfunction "DIR_8") (pintype "input"))
      (node (ref "JP2") (pin "25") (pinfunction "25_25") (pintype "passive"))
    )
    (net (code "6") (name "/DIR5") (class "Default")
      (node (ref "IC5") (pin "8") (pinfunction "DIR_8") (pintype "input"))
      (node (ref "JP2") (pin "31") (pinfunction "31_31") (pintype "passive"))
    )
    (net (code "7") (name "/DIR6") (class "Default")
      (node (ref "IC6") (pin "8") (pinfunction "DIR_8") (pintype "input"))
      (node (ref "JP2") (pin "8") (pinfunction "8_8") (pintype "passive"))
    )
    (net (code "8") (name "/DIR7") (class "Default")
      (node (ref "IC7") (pin "8") (pinfunction "DIR_8") (pintype "input"))
      (node (ref "JP2") (pin "14") (pinfunction "14_14") (pintype "passive"))
    )
    (net (code "9") (name "/DIR8") (class "Default")
      (node (ref "IC8") (pin "8") (pinfunction "DIR_8") (pintype "input"))
      (node (ref "JP2") (pin "20") (pinfunction "20_20") (pintype "passive"))
    )
    (net (code "10") (name "/DIR9") (class "Default")
      (node (ref "IC9") (pin "8") (pinfunction "DIR_8") (pintype "input"))
      (node (ref "JP2") (pin "26") (pinfunction "26_26") (pintype "passive"))
    )
    (net (code "11") (name "/DIR10") (class "Default")
      (node (ref "IC10") (pin "8") (pinfunction "DIR_8") (pintype "input"))
      (node (ref "JP2") (pin "32") (pinfunction "32_32") (pintype "passive"))
    )
    (net (code "12") (name "/DIR11") (class "Default")
      (node (ref "IC11") (pin "8") (pinfunction "DIR_8") (pintype "input"))
      (node (ref "JP3") (pin "6") (pinfunction "6_6") (pintype "passive"))
    )
    (net (code "13") (name "/DIR12") (class "Default")
      (node (ref "IC12") (pin "8") (pinfunction "DIR_8") (pintype "input"))
      (node (ref "JP3") (pin "3") (pinfunction "3_3") (pintype "passive"))
    )
    (net (code "14") (name "/DIR13") (class "Default")
      (node (ref "IC13") (pin "8") (pinfunction "DIR_8") (pintype "input"))
      (node (ref "JP4") (pin "8") (pinfunction "8_8") (pintype "passive"))
    )
    (net (code "15") (name "/DIR14") (class "Default")
      (node (ref "IC14") (pin "8") (pinfunction "DIR_8") (pintype "input"))
      (node (ref "JP4") (pin "5") (pinfunction "5_5") (pintype "passive"))
    )
    (net (code "16") (name "/DIR15") (class "Default")
      (node (ref "IC15") (pin "8") (pinfunction "DIR_8") (pintype "input"))
      (node (ref "JP4") (pin "2") (pinfunction "2_2") (pintype "passive"))
    )
    (net (code "17") (name "/GND1") (class "Default")
      (node (ref "IC1") (pin "9") (pinfunction "GND1_9") (pintype "power_in"))
      (node (ref "IC10") (pin "9") (pinfunction "GND1_9") (pintype "power_in"))
      (node (ref "IC11") (pin "9") (pinfunction "GND1_9") (pintype "power_in"))
      (node (ref "IC12") (pin "9") (pinfunction "GND1_9") (pintype "power_in"))
      (node (ref "IC13") (pin "9") (pinfunction "GND1_9") (pintype "power_in"))
      (node (ref "IC14") (pin "9") (pinfunction "GND1_9") (pintype "power_in"))
      (node (ref "IC15") (pin "9") (pinfunction "GND1_9") (pintype "power_in"))
      (node (ref "IC2") (pin "9") (pinfunction "GND1_9") (pintype "power_in"))
      (node (ref "IC3") (pin "9") (pinfunction "GND1_9") (pintype "power_in"))
      (node (ref "IC4") (pin "9") (pinfunction "GND1_9") (pintype "power_in"))
      (node (ref "IC5") (pin "9") (pinfunction "GND1_9") (pintype "power_in"))
      (node (ref "IC6") (pin "9") (pinfunction "GND1_9") (pintype "power_in"))
      (node (ref "IC7") (pin "9") (pinfunction "GND1_9") (pintype "power_in"))
      (node (ref "IC8") (pin "9") (pinfunction "GND1_9") (pintype "power_in"))
      (node (ref "IC9") (pin "9") (pinfunction "GND1_9") (pintype "power_in"))
      (node (ref "J1") (pin "2") (pinfunction "2_2") (pintype "passive"))
      (node (ref "SV1") (pin "2") (pinfunction "2_2") (pintype "passive"))
      (node (ref "SV1") (pin "4") (pinfunction "4_4") (pintype "passive"))
      (node (ref "SV10") (pin "2") (pinfunction "2_2") (pintype "passive"))
      (node (ref "SV10") (pin "4") (pinfunction "4_4") (pintype "passive"))
      (node (ref "SV11") (pin "2") (pinfunction "2_2") (pintype "passive"))
      (node (ref "SV11") (pin "4") (pinfunction "4_4") (pintype "passive"))
      (node (ref "SV12") (pin "2") (pinfunction "2_2") (pintype "passive"))
      (node (ref "SV12") (pin "4") (pinfunction "4_4") (pintype "passive"))
      (node (ref "SV13") (pin "2") (pinfunction "2_2") (pintype "passive"))
      (node (ref "SV13") (pin "4") (pinfunction "4_4") (pintype "passive"))
      (node (ref "SV14") (pin "2") (pinfunction "2_2") (pintype "passive"))
      (node (ref "SV14") (pin "4") (pinfunction "4_4") (pintype "passive"))
      (node (ref "SV15") (pin "2") (pinfunction "2_2") (pintype "passive"))
      (node (ref "SV15") (pin "4") (pinfunction "4_4") (pintype "passive"))
      (node (ref "SV2") (pin "2") (pinfunction "2_2") (pintype "passive"))
      (node (ref "SV2") (pin "4") (pinfunction "4_4") (pintype "passive"))
      (node (ref "SV3") (pin "2") (pinfunction "2_2") (pintype "passive"))
      (node (ref "SV3") (pin "4") (pinfunction "4_4") (pintype "passive"))
      (node (ref "SV4") (pin "2") (pinfunction "2_2") (pintype "passive"))
      (node (ref "SV4") (pin "4") (pinfunction "4_4") (pintype "passive"))
      (node (ref "SV5") (pin "2") (pinfunction "2_2") (pintype "passive"))
      (node (ref "SV5") (pin "4") (pinfunction "4_4") (pintype "passive"))
      (node (ref "SV6") (pin "2") (pinfunction "2_2") (pintype "passive"))
      (node (ref "SV6") (pin "4") (pinfunction "4_4") (pintype "passive"))
      (node (ref "SV7") (pin "2") (pinfunction "2_2") (pintype "passive"))
      (node (ref "SV7") (pin "4") (pinfunction "4_4") (pintype "passive"))
      (node (ref "SV8") (pin "2") (pinfunction "2_2") (pintype "passive"))
      (node (ref "SV8") (pin "4") (pinfunction "4_4") (pintype "passive"))
      (node (ref "SV9") (pin "2") (pinfunction "2_2") (pintype "passive"))
      (node (ref "SV9") (pin "4") (pinfunction "4_4") (pintype "passive"))
    )
    (net (code "18") (name "/GND2") (class "Default")
      (node (ref "C1") (pin "-") (pinfunction "-_-") (pintype "passive"))
      (node (ref "C10") (pin "-") (pinfunction "-_-") (pintype "passive"))
      (node (ref "C11") (pin "-") (pinfunction "-_-") (pintype "passive"))
      (node (ref "C12") (pin "-") (pinfunction "-_-") (pintype "passive"))
      (node (ref "C13") (pin "-") (pinfunction "-_-") (pintype "passive"))
      (node (ref "C14") (pin "-") (pinfunction "-_-") (pintype "passive"))
      (node (ref "C15") (pin "-") (pinfunction "-_-") (pintype "passive"))
      (node (ref "C2") (pin "-") (pinfunction "-_-") (pintype "passive"))
      (node (ref "C3") (pin "-") (pinfunction "-_-") (pintype "passive"))
      (node (ref "C4") (pin "-") (pinfunction "-_-") (pintype "passive"))
      (node (ref "C5") (pin "-") (pinfunction "-_-") (pintype "passive"))
      (node (ref "C6") (pin "-") (pinfunction "-_-") (pintype "passive"))
      (node (ref "C7") (pin "-") (pinfunction "-_-") (pintype "passive"))
      (node (ref "C8") (pin "-") (pinfunction "-_-") (pintype "passive"))
      (node (ref "C9") (pin "-") (pinfunction "-_-") (pintype "passive"))
      (node (ref "CR1") (pin "3") (pinfunction "3_3") (pintype "passive"))
      (node (ref "CR10") (pin "3") (pinfunction "3_3") (pintype "passive"))
      (node (ref "CR11") (pin "3") (pinfunction "3_3") (pintype "passive"))
      (node (ref "CR12") (pin "3") (pinfunction "3_3") (pintype "passive"))
      (node (ref "CR13") (pin "3") (pinfunction "3_3") (pintype "passive"))
      (node (ref "CR14") (pin "3") (pinfunction "3_3") (pintype "passive"))
      (node (ref "CR15") (pin "3") (pinfunction "3_3") (pintype "passive"))
      (node (ref "CR2") (pin "3") (pinfunction "3_3") (pintype "passive"))
      (node (ref "CR3") (pin "3") (pinfunction "3_3") (pintype "passive"))
      (node (ref "CR4") (pin "3") (pinfunction "3_3") (pintype "passive"))
      (node (ref "CR5") (pin "3") (pinfunction "3_3") (pintype "passive"))
      (node (ref "CR6") (pin "3") (pinfunction "3_3") (pintype "passive"))
      (node (ref "CR7") (pin "3") (pinfunction "3_3") (pintype "passive"))
      (node (ref "CR8") (pin "3") (pinfunction "3_3") (pintype "passive"))
      (node (ref "CR9") (pin "3") (pinfunction "3_3") (pintype "passive"))
      (node (ref "IC1") (pin "15") (pinfunction "GND2_15") (pintype "power_in"))
      (node (ref "IC10") (pin "15") (pinfunction "GND2_15") (pintype "power_in"))
      (node (ref "IC11") (pin "15") (pinfunction "GND2_15") (pintype "power_in"))
      (node (ref "IC12") (pin "15") (pinfunction "GND2_15") (pintype "power_in"))
      (node (ref "IC13") (pin "15") (pinfunction "GND2_15") (pintype "power_in"))
      (node (ref "IC14") (pin "15") (pinfunction "GND2_15") (pintype "power_in"))
      (node (ref "IC15") (pin "15") (pinfunction "GND2_15") (pintype "power_in"))
      (node (ref "IC2") (pin "15") (pinfunction "GND2_15") (pintype "power_in"))
      (node (ref "IC3") (pin "15") (pinfunction "GND2_15") (pintype "power_in"))
      (node (ref "IC4") (pin "15") (pinfunction "GND2_15") (pintype "power_in"))
      (node (ref "IC5") (pin "15") (pinfunction "GND2_15") (pintype "power_in"))
      (node (ref "IC6") (pin "15") (pinfunction "GND2_15") (pintype "power_in"))
      (node (ref "IC7") (pin "15") (pinfunction "GND2_15") (pintype "power_in"))
      (node (ref "IC8") (pin "15") (pinfunction "GND2_15") (pintype "power_in"))
      (node (ref "IC9") (pin "15") (pinfunction "GND2_15") (pintype "power_in"))
      (node (ref "J1") (pin "3") (pinfunction "3_3") (pintype "passive"))
    )
    (net (code "19") (name "/SLP1") (class "Default")
      (node (ref "IC1") (pin "6") (pinfunction "~{SLEEP}_6") (pintype "input"))
      (node (ref "JP2") (pin "3") (pinfunction "3_3") (pintype "passive"))
      (node (ref "R1") (pin "2") (pinfunction "2_2") (pintype "passive"))
    )
    (net (code "20") (name "/SLP2") (class "Default")
      (node (ref "IC2") (pin "6") (pinfunction "~{SLEEP}_6") (pintype "input"))
      (node (ref "JP2") (pin "9") (pinfunction "9_9") (pintype "passive"))
      (node (ref "R2") (pin "2") (pinfunction "2_2") (pintype "passive"))
    )
    (net (code "21") (name "/SLP3") (class "Default")
      (node (ref "IC3") (pin "6") (pinfunction "~{SLEEP}_6") (pintype "input"))
      (node (ref "JP2") (pin "15") (pinfunction "15_15") (pintype "passive"))
      (node (ref "R3") (pin "2") (pinfunction "2_2") (pintype "passive"))
    )
    (net (code "22") (name "/SLP4") (class "Default")
      (node (ref "IC4") (pin "6") (pinfunction "~{SLEEP}_6") (pintype "input"))
      (node (ref "JP2") (pin "21") (pinfunction "21_21") (pintype "passive"))
      (node (ref "R4") (pin "2") (pinfunction "2_2") (pintype "passive"))
    )
    (net (code "23") (name "/SLP5") (class "Default")
      (node (ref "IC5") (pin "6") (pinfunction "~{SLEEP}_6") (pintype "input"))
      (node (ref "JP2") (pin "27") (pinfunction "27_27") (pintype "passive"))
      (node (ref "R5") (pin "2") (pinfunction "2_2") (pintype "passive"))
    )
    (net (code "24") (name "/SLP6") (class "Default")
      (node (ref "IC6") (pin "6") (pinfunction "~{SLEEP}_6") (pintype "input"))
      (node (ref "JP2") (pin "4") (pinfunction "4_4") (pintype "passive"))
      (node (ref "R6") (pin "2") (pinfunction "2_2") (pintype "passive"))
    )
    (net (code "25") (name "/SLP7") (class "Default")
      (node (ref "IC7") (pin "6") (pinfunction "~{SLEEP}_6") (pintype "input"))
      (node (ref "JP2") (pin "10") (pinfunction "10_10") (pintype "passive"))
      (node (ref "R7") (pin "2") (pinfunction "2_2") (pintype "passive"))
    )
    (net (code "26") (name "/SLP8") (class "Default")
      (node (ref "IC8") (pin "6") (pinfunction "~{SLEEP}_6") (pintype "input"))
      (node (ref "JP2") (pin "16") (pinfunction "16_16") (pintype "passive"))
      (node (ref "R8") (pin "2") (pinfunction "2_2") (pintype "passive"))
    )
    (net (code "27") (name "/SLP9") (class "Default")
      (node (ref "IC9") (pin "6") (pinfunction "~{SLEEP}_6") (pintype "input"))
      (node (ref "JP2") (pin "22") (pinfunction "22_22") (pintype "passive"))
      (node (ref "R9") (pin "2") (pinfunction "2_2") (pintype "passive"))
    )
    (net (code "28") (name "/SLP10") (class "Default")
      (node (ref "IC10") (pin "6") (pinfunction "~{SLEEP}_6") (pintype "input"))
      (node (ref "JP2") (pin "28") (pinfunction "28_28") (pintype "passive"))
      (node (ref "R10") (pin "2") (pinfunction "2_2") (pintype "passive"))
    )
    (net (code "29") (name "/SLP11") (class "Default")
      (node (ref "IC11") (pin "6") (pinfunction "~{SLEEP}_6") (pintype "input"))
      (node (ref "JP3") (pin "8") (pinfunction "8_8") (pintype "passive"))
      (node (ref "R11") (pin "2") (pinfunction "2_2") (pintype "passive"))
    )
    (net (code "30") (name "/SLP12") (class "Default")
      (node (ref "IC12") (pin "6") (pinfunction "~{SLEEP}_6") (pintype "input"))
      (node (ref "JP3") (pin "5") (pinfunction "5_5") (pintype "passive"))
      (node (ref "R12") (pin "2") (pinfunction "2_2") (pintype "passive"))
    )
    (net (code "31") (name "/SLP13") (class "Default")
      (node (ref "IC13") (pin "6") (pinfunction "~{SLEEP}_6") (pintype "input"))
      (node (ref "JP3") (pin "2") (pinfunction "2_2") (pintype "passive"))
      (node (ref "R13") (pin "2") (pinfunction "2_2") (pintype "passive"))
    )
    (net (code "32") (name "/SLP14") (class "Default")
      (node (ref "IC14") (pin "6") (pinfunction "~{SLEEP}_6") (pintype "input"))
      (node (ref "JP4") (pin "7") (pinfunction "7_7") (pintype "passive"))
      (node (ref "R14") (pin "2") (pinfunction "2_2") (pintype "passive"))
    )
    (net (code "33") (name "/SLP15") (class "Default")
      (node (ref "IC15") (pin "6") (pinfunction "~{SLEEP}_6") (pintype "input"))
      (node (ref "JP4") (pin "4") (pinfunction "4_4") (pintype "passive"))
      (node (ref "R15") (pin "2") (pinfunction "2_2") (pintype "passive"))
    )
    (net (code "34") (name "/STEP1") (class "Default")
      (node (ref "IC1") (pin "7") (pinfunction "STEP_7") (pintype "input"))
      (node (ref "JP2") (pin "5") (pinfunction "5_5") (pintype "passive"))
    )
    (net (code "35") (name "/STEP2") (class "Default")
      (node (ref "IC2") (pin "7") (pinfunction "STEP_7") (pintype "input"))
      (node (ref "JP2") (pin "11") (pinfunction "11_11") (pintype "passive"))
    )
    (net (code "36") (name "/STEP3") (class "Default")
      (node (ref "IC3") (pin "7") (pinfunction "STEP_7") (pintype "input"))
      (node (ref "JP2") (pin "17") (pinfunction "17_17") (pintype "passive"))
    )
    (net (code "37") (name "/STEP4") (class "Default")
      (node (ref "IC4") (pin "7") (pinfunction "STEP_7") (pintype "input"))
      (node (ref "JP2") (pin "23") (pinfunction "23_23") (pintype "passive"))
    )
    (net (code "38") (name "/STEP5") (class "Default")
      (node (ref "IC5") (pin "7") (pinfunction "STEP_7") (pintype "input"))
      (node (ref "JP2") (pin "29") (pinfunction "29_29") (pintype "passive"))
    )
    (net (code "39") (name "/STEP6") (class "Default")
      (node (ref "IC6") (pin "7") (pinfunction "STEP_7") (pintype "input"))
      (node (ref "JP2") (pin "6") (pinfunction "6_6") (pintype "passive"))
    )
    (net (code "40") (name "/STEP7") (class "Default")
      (node (ref "IC7") (pin "7") (pinfunction "STEP_7") (pintype "input"))
      (node (ref "JP2") (pin "12") (pinfunction "12_12") (pintype "passive"))
    )
    (net (code "41") (name "/STEP8") (class "Default")
      (node (ref "IC8") (pin "7") (pinfunction "STEP_7") (pintype "input"))
      (node (ref "JP2") (pin "18") (pinfunction "18_18") (pintype "passive"))
    )
    (net (code "42") (name "/STEP9") (class "Default")
      (node (ref "IC9") (pin "7") (pinfunction "STEP_7") (pintype "input"))
      (node (ref "JP2") (pin "24") (pinfunction "24_24") (pintype "passive"))
    )
    (net (code "43") (name "/STEP10") (class "Default")
      (node (ref "IC10") (pin "7") (pinfunction "STEP_7") (pintype "input"))
      (node (ref "JP2") (pin "30") (pinfunction "30_30") (pintype "passive"))
    )
    (net (code "44") (name "/STEP11") (class "Default")
      (node (ref "IC11") (pin "7") (pinfunction "STEP_7") (pintype "input"))
      (node (ref "JP3") (pin "7") (pinfunction "7_7") (pintype "passive"))
    )
    (net (code "45") (name "/STEP12") (class "Default")
      (node (ref "IC12") (pin "7") (pinfunction "STEP_7") (pintype "input"))
      (node (ref "JP3") (pin "4") (pinfunction "4_4") (pintype "passive"))
    )
    (net (code "46") (name "/STEP13") (class "Default")
      (node (ref "IC13") (pin "7") (pinfunction "STEP_7") (pintype "input"))
      (node (ref "JP3") (pin "1") (pinfunction "1_1") (pintype "passive"))
    )
    (net (code "47") (name "/STEP14") (class "Default")
      (node (ref "IC14") (pin "7") (pinfunction "STEP_7") (pintype "input"))
      (node (ref "JP4") (pin "6") (pinfunction "6_6") (pintype "passive"))
    )
    (net (code "48") (name "/STEP15") (class "Default")
      (node (ref "IC15") (pin "7") (pinfunction "STEP_7") (pintype "input"))
      (node (ref "JP4") (pin "3") (pinfunction "3_3") (pintype "passive"))
    )
    (net (code "49") (name "/VMOT1") (class "Default")
      (node (ref "C1") (pin "+") (pinfunction "+_+") (pintype "passive"))
      (node (ref "CR1") (pin "1") (pinfunction "1_1") (pintype "bidirectional"))
      (node (ref "CR1") (pin "2") (pinfunction "2_2") (pintype "bidirectional"))
      (node (ref "F1") (pin "2") (pinfunction "2_2") (pintype "passive"))
      (node (ref "IC1") (pin "16") (pinfunction "VMOT_16") (pintype "power_in"))
    )
    (net (code "50") (name "/VMOT2") (class "Default")
      (node (ref "C2") (pin "+") (pinfunction "+_+") (pintype "passive"))
      (node (ref "CR2") (pin "1") (pinfunction "1_1") (pintype "bidirectional"))
      (node (ref "CR2") (pin "2") (pinfunction "2_2") (pintype "bidirectional"))
      (node (ref "F2") (pin "2") (pinfunction "2_2") (pintype "passive"))
      (node (ref "IC2") (pin "16") (pinfunction "VMOT_16") (pintype "power_in"))
    )
    (net (code "51") (name "/VMOT3") (class "Default")
      (node (ref "C3") (pin "+") (pinfunction "+_+") (pintype "passive"))
      (node (ref "CR3") (pin "1") (pinfunction "1_1") (pintype "bidirectional"))
      (node (ref "CR3") (pin "2") (pinfunction "2_2") (pintype "bidirectional"))
      (node (ref "F3") (pin "2") (pinfunction "2_2") (pintype "passive"))
      (node (ref "IC3") (pin "16") (pinfunction "VMOT_16") (pintype "power_in"))
    )
    (net (code "52") (name "/VMOT4") (class "Default")
      (node (ref "C4") (pin "+") (pinfunction "+_+") (pintype "passive"))
      (node (ref "CR4") (pin "1") (pinfunction "1_1") (pintype "bidirectional"))
      (node (ref "CR4") (pin "2") (pinfunction "2_2") (pintype "bidirectional"))
      (node (ref "F4") (pin "2") (pinfunction "2_2") (pintype "passive"))
      (node (ref "IC4") (pin "16") (pinfunction "VMOT_16") (pintype "power_in"))
    )
    (net (code "53") (name "/VMOT5") (class "Default")
      (node (ref "C5") (pin "+") (pinfunction "+_+") (pintype "passive"))
      (node (ref "CR5") (pin "1") (pinfunction "1_1") (pintype "bidirectional"))
      (node (ref "CR5") (pin "2") (pinfunction "2_2") (pintype "bidirectional"))
      (node (ref "F5") (pin "2") (pinfunction "2_2") (pintype "passive"))
      (node (ref "IC5") (pin "16") (pinfunction "VMOT_16") (pintype "power_in"))
    )
    (net (code "54") (name "/VMOT6") (class "Default")
      (node (ref "C6") (pin "+") (pinfunction "+_+") (pintype "passive"))
      (node (ref "CR6") (pin "1") (pinfunction "1_1") (pintype "bidirectional"))
      (node (ref "CR6") (pin "2") (pinfunction "2_2") (pintype "bidirectional"))
      (node (ref "F6") (pin "2") (pinfunction "2_2") (pintype "passive"))
      (node (ref "IC6") (pin "16") (pinfunction "VMOT_16") (pintype "power_in"))
    )
    (net (code "55") (name "/VMOT7") (class "Default")
      (node (ref "C7") (pin "+") (pinfunction "+_+") (pintype "passive"))
      (node (ref "CR7") (pin "1") (pinfunction "1_1") (pintype "bidirectional"))
      (node (ref "CR7") (pin "2") (pinfunction "2_2") (pintype "bidirectional"))
      (node (ref "F7") (pin "2") (pinfunction "2_2") (pintype "passive"))
      (node (ref "IC7") (pin "16") (pinfunction "VMOT_16") (pintype "power_in"))
    )
    (net (code "56") (name "/VMOT8") (class "Default")
      (node (ref "C8") (pin "+") (pinfunction "+_+") (pintype "passive"))
      (node (ref "CR8") (pin "1") (pinfunction "1_1") (pintype "bidirectional"))
      (node (ref "CR8") (pin "2") (pinfunction "2_2") (pintype "bidirectional"))
      (node (ref "F8") (pin "2") (pinfunction "2_2") (pintype "passive"))
      (node (ref "IC8") (pin "16") (pinfunction "VMOT_16") (pintype "power_in"))
    )
    (net (code "57") (name "/VMOT9") (class "Default")
      (node (ref "C9") (pin "+") (pinfunction "+_+") (pintype "passive"))
      (node (ref "CR9") (pin "1") (pinfunction "1_1") (pintype "bidirectional"))
      (node (ref "CR9") (pin "2") (pinfunction "2_2") (pintype "bidirectional"))
      (node (ref "F9") (pin "2") (pinfunction "2_2") (pintype "passive"))
      (node (ref "IC9") (pin "16") (pinfunction "VMOT_16") (pintype "power_in"))
    )
    (net (code "58") (name "/VMOT10") (class "Default")
      (node (ref "C10") (pin "+") (pinfunction "+_+") (pintype "passive"))
      (node (ref "CR10") (pin "1") (pinfunction "1_1") (pintype "bidirectional"))
      (node (ref "CR10") (pin "2") (pinfunction "2_2") (pintype "bidirectional"))
      (node (ref "F10") (pin "2") (pinfunction "2_2") (pintype "passive"))
      (node (ref "IC10") (pin "16") (pinfunction "VMOT_16") (pintype "power_in"))
    )
    (net (code "59") (name "/VMOT11") (class "Default")
      (node (ref "C11") (pin "+") (pinfunction "+_+") (pintype "passive"))
      (node (ref "CR11") (pin "1") (pinfunction "1_1") (pintype "bidirectional"))
      (node (ref "CR11") (pin "2") (pinfunction "2_2") (pintype "bidirectional"))
      (node (ref "F11") (pin "2") (pinfunction "2_2") (pintype "passive"))
      (node (ref "IC11") (pin "16") (pinfunction "VMOT_16") (pintype "power_in"))
    )
    (net (code "60") (name "/VMOT12") (class "Default")
      (node (ref "C12") (pin "+") (pinfunction "+_+") (pintype "passive"))
      (node (ref "CR12") (pin "1") (pinfunction "1_1") (pintype "bidirectional"))
      (node (ref "CR12") (pin "2") (pinfunction "2_2") (pintype "bidirectional"))
      (node (ref "F12") (pin "2") (pinfunction "2_2") (pintype "passive"))
      (node (ref "IC12") (pin "16") (pinfunction "VMOT_16") (pintype "power_in"))
    )
    (net (code "61") (name "/VMOT13") (class "Default")
      (node (ref "C13") (pin "+") (pinfunction "+_+") (pintype "passive"))
      (node (ref "CR13") (pin "1") (pinfunction "1_1") (pintype "bidirectional"))
      (node (ref "CR13") (pin "2") (pinfunction "2_2") (pintype "bidirectional"))
      (node (ref "F13") (pin "2") (pinfunction "2_2") (pintype "passive"))
      (node (ref "IC13") (pin "16") (pinfunction "VMOT_16") (pintype "power_in"))
    )
    (net (code "62") (name "/VMOT14") (class "Default")
      (node (ref "C14") (pin "+") (pinfunction "+_+") (pintype "passive"))
      (node (ref "CR14") (pin "1") (pinfunction "1_1") (pintype "bidirectional"))
      (node (ref "CR14") (pin "2") (pinfunction "2_2") (pintype "bidirectional"))
      (node (ref "F14") (pin "2") (pinfunction "2_2") (pintype "passive"))
      (node (ref "IC14") (pin "16") (pinfunction "VMOT_16") (pintype "power_in"))
    )
    (net (code "63") (name "/VMOT15") (class "Default")
      (node (ref "C15") (pin "+") (pinfunction "+_+") (pintype "passive"))
      (node (ref "CR15") (pin "1") (pinfunction "1_1") (pintype "bidirectional"))
      (node (ref "CR15") (pin "2") (pinfunction "2_2") (pintype "bidirectional"))
      (node (ref "F15") (pin "2") (pinfunction "2_2") (pintype "passive"))
      (node (ref "IC15") (pin "16") (pinfunction "VMOT_16") (pintype "power_in"))
    )
    (net (code "64") (name "Net-(F1-Pad1)") (class "Default")
      (node (ref "F1") (pin "1") (pinfunction "1_1") (pintype "passive"))
      (node (ref "F10") (pin "1") (pinfunction "1_1") (pintype "passive"))
      (node (ref "F11") (pin "1") (pinfunction "1_1") (pintype "passive"))
      (node (ref "F12") (pin "1") (pinfunction "1_1") (pintype "passive"))
      (node (ref "F13") (pin "1") (pinfunction "1_1") (pintype "passive"))
      (node (ref "F14") (pin "1") (pinfunction "1_1") (pintype "passive"))
      (node (ref "F15") (pin "1") (pinfunction "1_1") (pintype "passive"))
      (node (ref "F2") (pin "1") (pinfunction "1_1") (pintype "passive"))
      (node (ref "F3") (pin "1") (pinfunction "1_1") (pintype "passive"))
      (node (ref "F4") (pin "1") (pinfunction "1_1") (pintype "passive"))
      (node (ref "F5") (pin "1") (pinfunction "1_1") (pintype "passive"))
      (node (ref "F6") (pin "1") (pinfunction "1_1") (pintype "passive"))
      (node (ref "F7") (pin "1") (pinfunction "1_1") (pintype "passive"))
      (node (ref "F8") (pin "1") (pinfunction "1_1") (pintype "passive"))
      (node (ref "F9") (pin "1") (pinfunction "1_1") (pintype "passive"))
      (node (ref "J1") (pin "4") (pinfunction "4_4") (pintype "passive"))
    )
    (net (code "65") (name "Net-(IC1-A1)") (class "Default")
      (node (ref "IC1") (pin "12") (pinfunction "A1_12") (pintype "output"))
      (node (ref "J2") (pin "3") (pinfunction "3_3") (pintype "passive"))
    )
    (net (code "66") (name "Net-(IC1-A2)") (class "Default")
      (node (ref "IC1") (pin "11") (pinfunction "A2_11") (pintype "output"))
      (node (ref "J2") (pin "4") (pinfunction "4_4") (pintype "passive"))
    )
    (net (code "67") (name "Net-(IC1-B1)") (class "Default")
      (node (ref "IC1") (pin "13") (pinfunction "B1_13") (pintype "output"))
      (node (ref "J2") (pin "2") (pinfunction "2_2") (pintype "passive"))
    )
    (net (code "68") (name "Net-(IC1-B2)") (class "Default")
      (node (ref "IC1") (pin "14") (pinfunction "B2_14") (pintype "output"))
      (node (ref "J2") (pin "1") (pinfunction "1_1") (pintype "passive"))
    )
    (net (code "69") (name "Net-(IC1-I1)") (class "Default")
      (node (ref "IC1") (pin "4") (pinfunction "I1_4") (pintype "passive"))
      (node (ref "SV1") (pin "3") (pinfunction "3_3") (pintype "passive"))
    )
    (net (code "70") (name "Net-(IC1-I2)") (class "Default")
      (node (ref "IC1") (pin "5") (pinfunction "I2_5") (pintype "passive"))
      (node (ref "SV1") (pin "1") (pinfunction "1_1") (pintype "passive"))
    )
    (net (code "71") (name "Net-(IC1-MS1)") (class "Default")
      (node (ref "IC1") (pin "2") (pinfunction "MS1_2") (pintype "passive"))
      (node (ref "SV1") (pin "7") (pinfunction "7_7") (pintype "passive"))
    )
    (net (code "72") (name "Net-(IC1-MS2)") (class "Default")
      (node (ref "IC1") (pin "3") (pinfunction "MS2_3") (pintype "passive"))
      (node (ref "SV1") (pin "5") (pinfunction "5_5") (pintype "passive"))
    )
    (net (code "73") (name "Net-(IC1-~{ENBL})") (class "Default")
      (node (ref "IC1") (pin "1") (pinfunction "~{ENBL}_1") (pintype "passive"))
      (node (ref "SV1") (pin "9") (pinfunction "9_9") (pintype "passive"))
    )
    (net (code "74") (name "Net-(IC2-A1)") (class "Default")
      (node (ref "IC2") (pin "12") (pinfunction "A1_12") (pintype "output"))
      (node (ref "J3") (pin "3") (pinfunction "3_3") (pintype "passive"))
    )
    (net (code "75") (name "Net-(IC2-A2)") (class "Default")
      (node (ref "IC2") (pin "11") (pinfunction "A2_11") (pintype "output"))
      (node (ref "J3") (pin "4") (pinfunction "4_4") (pintype "passive"))
    )
    (net (code "76") (name "Net-(IC2-B1)") (class "Default")
      (node (ref "IC2") (pin "13") (pinfunction "B1_13") (pintype "output"))
      (node (ref "J3") (pin "2") (pinfunction "2_2") (pintype "passive"))
    )
    (net (code "77") (name "Net-(IC2-B2)") (class "Default")
      (node (ref "IC2") (pin "14") (pinfunction "B2_14") (pintype "output"))
      (node (ref "J3") (pin "1") (pinfunction "1_1") (pintype "passive"))
    )
    (net (code "78") (name "Net-(IC2-I1)") (class "Default")
      (node (ref "IC2") (pin "4") (pinfunction "I1_4") (pintype "passive"))
      (node (ref "SV2") (pin "3") (pinfunction "3_3") (pintype "passive"))
    )
    (net (code "79") (name "Net-(IC2-I2)") (class "Default")
      (node (ref "IC2") (pin "5") (pinfunction "I2_5") (pintype "passive"))
      (node (ref "SV2") (pin "1") (pinfunction "1_1") (pintype "passive"))
    )
    (net (code "80") (name "Net-(IC2-MS1)") (class "Default")
      (node (ref "IC2") (pin "2") (pinfunction "MS1_2") (pintype "passive"))
      (node (ref "SV2") (pin "7") (pinfunction "7_7") (pintype "passive"))
    )
    (net (code "81") (name "Net-(IC2-MS2)") (class "Default")
      (node (ref "IC2") (pin "3") (pinfunction "MS2_3") (pintype "passive"))
      (node (ref "SV2") (pin "5") (pinfunction "5_5") (pintype "passive"))
    )
    (net (code "82") (name "Net-(IC2-~{ENBL})") (class "Default")
      (node (ref "IC2") (pin "1") (pinfunction "~{ENBL}_1") (pintype "passive"))
      (node (ref "SV2") (pin "9") (pinfunction "9_9") (pintype "passive"))
    )
    (net (code "83") (name "Net-(IC3-A1)") (class "Default")
      (node (ref "IC3") (pin "12") (pinfunction "A1_12") (pintype "output"))
      (node (ref "J4") (pin "3") (pinfunction "3_3") (pintype "passive"))
    )
    (net (code "84") (name "Net-(IC3-A2)") (class "Default")
      (node (ref "IC3") (pin "11") (pinfunction "A2_11") (pintype "output"))
      (node (ref "J4") (pin "4") (pinfunction "4_4") (pintype "passive"))
    )
    (net (code "85") (name "Net-(IC3-B1)") (class "Default")
      (node (ref "IC3") (pin "13") (pinfunction "B1_13") (pintype "output"))
      (node (ref "J4") (pin "2") (pinfunction "2_2") (pintype "passive"))
    )
    (net (code "86") (name "Net-(IC3-B2)") (class "Default")
      (node (ref "IC3") (pin "14") (pinfunction "B2_14") (pintype "output"))
      (node (ref "J4") (pin "1") (pinfunction "1_1") (pintype "passive"))
    )
    (net (code "87") (name "Net-(IC3-I1)") (class "Default")
      (node (ref "IC3") (pin "4") (pinfunction "I1_4") (pintype "passive"))
      (node (ref "SV3") (pin "3") (pinfunction "3_3") (pintype "passive"))
    )
    (net (code "88") (name "Net-(IC3-I2)") (class "Default")
      (node (ref "IC3") (pin "5") (pinfunction "I2_5") (pintype "passive"))
      (node (ref "SV3") (pin "1") (pinfunction "1_1") (pintype "passive"))
    )
    (net (code "89") (name "Net-(IC3-MS1)") (class "Default")
      (node (ref "IC3") (pin "2") (pinfunction "MS1_2") (pintype "passive"))
      (node (ref "SV3") (pin "7") (pinfunction "7_7") (pintype "passive"))
    )
    (net (code "90") (name "Net-(IC3-MS2)") (class "Default")
      (node (ref "IC3") (pin "3") (pinfunction "MS2_3") (pintype "passive"))
      (node (ref "SV3") (pin "5") (pinfunction "5_5") (pintype "passive"))
    )
    (net (code "91") (name "Net-(IC3-~{ENBL})") (class "Default")
      (node (ref "IC3") (pin "1") (pinfunction "~{ENBL}_1") (pintype "passive"))
      (node (ref "SV3") (pin "9") (pinfunction "9_9") (pintype "passive"))
    )
    (net (code "92") (name "Net-(IC4-A1)") (class "Default")
      (node (ref "IC4") (pin "12") (pinfunction "A1_12") (pintype "output"))
      (node (ref "J5") (pin "3") (pinfunction "3_3") (pintype "passive"))
    )
    (net (code "93") (name "Net-(IC4-A2)") (class "Default")
      (node (ref "IC4") (pin "11") (pinfunction "A2_11") (pintype "output"))
      (node (ref "J5") (pin "4") (pinfunction "4_4") (pintype "passive"))
    )
    (net (code "94") (name "Net-(IC4-B1)") (class "Default")
      (node (ref "IC4") (pin "13") (pinfunction "B1_13") (pintype "output"))
      (node (ref "J5") (pin "2") (pinfunction "2_2") (pintype "passive"))
    )
    (net (code "95") (name "Net-(IC4-B2)") (class "Default")
      (node (ref "IC4") (pin "14") (pinfunction "B2_14") (pintype "output"))
      (node (ref "J5") (pin "1") (pinfunction "1_1") (pintype "passive"))
    )
    (net (code "96") (name "Net-(IC4-I1)") (class "Default")
      (node (ref "IC4") (pin "4") (pinfunction "I1_4") (pintype "passive"))
      (node (ref "SV4") (pin "3") (pinfunction "3_3") (pintype "passive"))
    )
    (net (code "97") (name "Net-(IC4-I2)") (class "Default")
      (node (ref "IC4") (pin "5") (pinfunction "I2_5") (pintype "passive"))
      (node (ref "SV4") (pin "1") (pinfunction "1_1") (pintype "passive"))
    )
    (net (code "98") (name "Net-(IC4-MS1)") (class "Default")
      (node (ref "IC4") (pin "2") (pinfunction "MS1_2") (pintype "passive"))
      (node (ref "SV4") (pin "7") (pinfunction "7_7") (pintype "passive"))
    )
    (net (code "99") (name "Net-(IC4-MS2)") (class "Default")
      (node (ref "IC4") (pin "3") (pinfunction "MS2_3") (pintype "passive"))
      (node (ref "SV4") (pin "5") (pinfunction "5_5") (pintype "passive"))
    )
    (net (code "100") (name "Net-(IC4-~{ENBL})") (class "Default")
      (node (ref "IC4") (pin "1") (pinfunction "~{ENBL}_1") (pintype "passive"))
      (node (ref "SV4") (pin "9") (pinfunction "9_9") (pintype "passive"))
    )
    (net (code "101") (name "Net-(IC5-A1)") (class "Default")
      (node (ref "IC5") (pin "12") (pinfunction "A1_12") (pintype "output"))
      (node (ref "J6") (pin "3") (pinfunction "3_3") (pintype "passive"))
    )
    (net (code "102") (name "Net-(IC5-A2)") (class "Default")
      (node (ref "IC5") (pin "11") (pinfunction "A2_11") (pintype "output"))
      (node (ref "J6") (pin "4") (pinfunction "4_4") (pintype "passive"))
    )
    (net (code "103") (name "Net-(IC5-B1)") (class "Default")
      (node (ref "IC5") (pin "13") (pinfunction "B1_13") (pintype "output"))
      (node (ref "J6") (pin "2") (pinfunction "2_2") (pintype "passive"))
    )
    (net (code "104") (name "Net-(IC5-B2)") (class "Default")
      (node (ref "IC5") (pin "14") (pinfunction "B2_14") (pintype "output"))
      (node (ref "J6") (pin "1") (pinfunction "1_1") (pintype "passive"))
    )
    (net (code "105") (name "Net-(IC5-I1)") (class "Default")
      (node (ref "IC5") (pin "4") (pinfunction "I1_4") (pintype "passive"))
      (node (ref "SV5") (pin "3") (pinfunction "3_3") (pintype "passive"))
    )
    (net (code "106") (name "Net-(IC5-I2)") (class "Default")
      (node (ref "IC5") (pin "5") (pinfunction "I2_5") (pintype "passive"))
      (node (ref "SV5") (pin "1") (pinfunction "1_1") (pintype "passive"))
    )
    (net (code "107") (name "Net-(IC5-MS1)") (class "Default")
      (node (ref "IC5") (pin "2") (pinfunction "MS1_2") (pintype "passive"))
      (node (ref "SV5") (pin "7") (pinfunction "7_7") (pintype "passive"))
    )
    (net (code "108") (name "Net-(IC5-MS2)") (class "Default")
      (node (ref "IC5") (pin "3") (pinfunction "MS2_3") (pintype "passive"))
      (node (ref "SV5") (pin "5") (pinfunction "5_5") (pintype "passive"))
    )
    (net (code "109") (name "Net-(IC5-~{ENBL})") (class "Default")
      (node (ref "IC5") (pin "1") (pinfunction "~{ENBL}_1") (pintype "passive"))
      (node (ref "SV5") (pin "9") (pinfunction "9_9") (pintype "passive"))
    )
    (net (code "110") (name "Net-(IC6-A1)") (class "Default")
      (node (ref "IC6") (pin "12") (pinfunction "A1_12") (pintype "output"))
      (node (ref "J7") (pin "3") (pinfunction "3_3") (pintype "passive"))
    )
    (net (code "111") (name "Net-(IC6-A2)") (class "Default")
      (node (ref "IC6") (pin "11") (pinfunction "A2_11") (pintype "output"))
      (node (ref "J7") (pin "4") (pinfunction "4_4") (pintype "passive"))
    )
    (net (code "112") (name "Net-(IC6-B1)") (class "Default")
      (node (ref "IC6") (pin "13") (pinfunction "B1_13") (pintype "output"))
      (node (ref "J7") (pin "2") (pinfunction "2_2") (pintype "passive"))
    )
    (net (code "113") (name "Net-(IC6-B2)") (class "Default")
      (node (ref "IC6") (pin "14") (pinfunction "B2_14") (pintype "output"))
      (node (ref "J7") (pin "1") (pinfunction "1_1") (pintype "passive"))
    )
    (net (code "114") (name "Net-(IC6-I1)") (class "Default")
      (node (ref "IC6") (pin "4") (pinfunction "I1_4") (pintype "passive"))
      (node (ref "SV6") (pin "3") (pinfunction "3_3") (pintype "passive"))
    )
    (net (code "115") (name "Net-(IC6-I2)") (class "Default")
      (node (ref "IC6") (pin "5") (pinfunction "I2_5") (pintype "passive"))
      (node (ref "SV6") (pin "1") (pinfunction "1_1") (pintype "passive"))
    )
    (net (code "116") (name "Net-(IC6-MS1)") (class "Default")
      (node (ref "IC6") (pin "2") (pinfunction "MS1_2") (pintype "passive"))
      (node (ref "SV6") (pin "7") (pinfunction "7_7") (pintype "passive"))
    )
    (net (code "117") (name "Net-(IC6-MS2)") (class "Default")
      (node (ref "IC6") (pin "3") (pinfunction "MS2_3") (pintype "passive"))
      (node (ref "SV6") (pin "5") (pinfunction "5_5") (pintype "passive"))
    )
    (net (code "118") (name "Net-(IC6-~{ENBL})") (class "Default")
      (node (ref "IC6") (pin "1") (pinfunction "~{ENBL}_1") (pintype "passive"))
      (node (ref "SV6") (pin "9") (pinfunction "9_9") (pintype "passive"))
    )
    (net (code "119") (name "Net-(IC7-A1)") (class "Default")
      (node (ref "IC7") (pin "12") (pinfunction "A1_12") (pintype "output"))
      (node (ref "J8") (pin "3") (pinfunction "3_3") (pintype "passive"))
    )
    (net (code "120") (name "Net-(IC7-A2)") (class "Default")
      (node (ref "IC7") (pin "11") (pinfunction "A2_11") (pintype "output"))
      (node (ref "J8") (pin "4") (pinfunction "4_4") (pintype "passive"))
    )
    (net (code "121") (name "Net-(IC7-B1)") (class "Default")
      (node (ref "IC7") (pin "13") (pinfunction "B1_13") (pintype "output"))
      (node (ref "J8") (pin "2") (pinfunction "2_2") (pintype "passive"))
    )
    (net (code "122") (name "Net-(IC7-B2)") (class "Default")
      (node (ref "IC7") (pin "14") (pinfunction "B2_14") (pintype "output"))
      (node (ref "J8") (pin "1") (pinfunction "1_1") (pintype "passive"))
    )
    (net (code "123") (name "Net-(IC7-I1)") (class "Default")
      (node (ref "IC7") (pin "4") (pinfunction "I1_4") (pintype "passive"))
      (node (ref "SV7") (pin "3") (pinfunction "3_3") (pintype "passive"))
    )
    (net (code "124") (name "Net-(IC7-I2)") (class "Default")
      (node (ref "IC7") (pin "5") (pinfunction "I2_5") (pintype "passive"))
      (node (ref "SV7") (pin "1") (pinfunction "1_1") (pintype "passive"))
    )
    (net (code "125") (name "Net-(IC7-MS1)") (class "Default")
      (node (ref "IC7") (pin "2") (pinfunction "MS1_2") (pintype "passive"))
      (node (ref "SV7") (pin "7") (pinfunction "7_7") (pintype "passive"))
    )
    (net (code "126") (name "Net-(IC7-MS2)") (class "Default")
      (node (ref "IC7") (pin "3") (pinfunction "MS2_3") (pintype "passive"))
      (node (ref "SV7") (pin "5") (pinfunction "5_5") (pintype "passive"))
    )
    (net (code "127") (name "Net-(IC7-~{ENBL})") (class "Default")
      (node (ref "IC7") (pin "1") (pinfunction "~{ENBL}_1") (pintype "passive"))
      (node (ref "SV7") (pin "9") (pinfunction "9_9") (pintype "passive"))
    )
    (net (code "128") (name "Net-(IC8-A1)") (class "Default")
      (node (ref "IC8") (pin "12") (pinfunction "A1_12") (pintype "output"))
      (node (ref "J9") (pin "3") (pinfunction "3_3") (pintype "passive"))
    )
    (net (code "129") (name "Net-(IC8-A2)") (class "Default")
      (node (ref "IC8") (pin "11") (pinfunction "A2_11") (pintype "output"))
      (node (ref "J9") (pin "4") (pinfunction "4_4") (pintype "passive"))
    )
    (net (code "130") (name "Net-(IC8-B1)") (class "Default")
      (node (ref "IC8") (pin "13") (pinfunction "B1_13") (pintype "output"))
      (node (ref "J9") (pin "2") (pinfunction "2_2") (pintype "passive"))
    )
    (net (code "131") (name "Net-(IC8-B2)") (class "Default")
      (node (ref "IC8") (pin "14") (pinfunction "B2_14") (pintype "output"))
      (node (ref "J9") (pin "1") (pinfunction "1_1") (pintype "passive"))
    )
    (net (code "132") (name "Net-(IC8-I1)") (class "Default")
      (node (ref "IC8") (pin "4") (pinfunction "I1_4") (pintype "passive"))
      (node (ref "SV8") (pin "3") (pinfunction "3_3") (pintype "passive"))
    )
    (net (code "133") (name "Net-(IC8-I2)") (class "Default")
      (node (ref "IC8") (pin "5") (pinfunction "I2_5") (pintype "passive"))
      (node (ref "SV8") (pin "1") (pinfunction "1_1") (pintype "passive"))
    )
    (net (code "134") (name "Net-(IC8-MS1)") (class "Default")
      (node (ref "IC8") (pin "2") (pinfunction "MS1_2") (pintype "passive"))
      (node (ref "SV8") (pin "7") (pinfunction "7_7") (pintype "passive"))
    )
    (net (code "135") (name "Net-(IC8-MS2)") (class "Default")
      (node (ref "IC8") (pin "3") (pinfunction "MS2_3") (pintype "passive"))
      (node (ref "SV8") (pin "5") (pinfunction "5_5") (pintype "passive"))
    )
    (net (code "136") (name "Net-(IC8-~{ENBL})") (class "Default")
      (node (ref "IC8") (pin "1") (pinfunction "~{ENBL}_1") (pintype "passive"))
      (node (ref "SV8") (pin "9") (pinfunction "9_9") (pintype "passive"))
    )
    (net (code "137") (name "Net-(IC9-A1)") (class "Default")
      (node (ref "IC9") (pin "12") (pinfunction "A1_12") (pintype "output"))
      (node (ref "J10") (pin "3") (pinfunction "3_3") (pintype "passive"))
    )
    (net (code "138") (name "Net-(IC9-A2)") (class "Default")
      (node (ref "IC9") (pin "11") (pinfunction "A2_11") (pintype "output"))
      (node (ref "J10") (pin "4") (pinfunction "4_4") (pintype "passive"))
    )
    (net (code "139") (name "Net-(IC9-B1)") (class "Default")
      (node (ref "IC9") (pin "13") (pinfunction "B1_13") (pintype "output"))
      (node (ref "J10") (pin "2") (pinfunction "2_2") (pintype "passive"))
    )
    (net (code "140") (name "Net-(IC9-B2)") (class "Default")
      (node (ref "IC9") (pin "14") (pinfunction "B2_14") (pintype "output"))
      (node (ref "J10") (pin "1") (pinfunction "1_1") (pintype "passive"))
    )
    (net (code "141") (name "Net-(IC9-I1)") (class "Default")
      (node (ref "IC9") (pin "4") (pinfunction "I1_4") (pintype "passive"))
      (node (ref "SV9") (pin "3") (pinfunction "3_3") (pintype "passive"))
    )
    (net (code "142") (name "Net-(IC9-I2)") (class "Default")
      (node (ref "IC9") (pin "5") (pinfunction "I2_5") (pintype "passive"))
      (node (ref "SV9") (pin "1") (pinfunction "1_1") (pintype "passive"))
    )
    (net (code "143") (name "Net-(IC9-MS1)") (class "Default")
      (node (ref "IC9") (pin "2") (pinfunction "MS1_2") (pintype "passive"))
      (node (ref "SV9") (pin "7") (pinfunction "7_7") (pintype "passive"))
    )
    (net (code "144") (name "Net-(IC9-MS2)") (class "Default")
      (node (ref "IC9") (pin "3") (pinfunction "MS2_3") (pintype "passive"))
      (node (ref "SV9") (pin "5") (pinfunction "5_5") (pintype "passive"))
    )
    (net (code "145") (name "Net-(IC9-~{ENBL})") (class "Default")
      (node (ref "IC9") (pin "1") (pinfunction "~{ENBL}_1") (pintype "passive"))
      (node (ref "SV9") (pin "9") (pinfunction "9_9") (pintype "passive"))
    )
    (net (code "146") (name "Net-(IC10-A1)") (class "Default")
      (node (ref "IC10") (pin "12") (pinfunction "A1_12") (pintype "output"))
      (node (ref "J11") (pin "3") (pinfunction "3_3") (pintype "passive"))
    )
    (net (code "147") (name "Net-(IC10-A2)") (class "Default")
      (node (ref "IC10") (pin "11") (pinfunction "A2_11") (pintype "output"))
      (node (ref "J11") (pin "4") (pinfunction "4_4") (pintype "passive"))
    )
    (net (code "148") (name "Net-(IC10-B1)") (class "Default")
      (node (ref "IC10") (pin "13") (pinfunction "B1_13") (pintype "output"))
      (node (ref "J11") (pin "2") (pinfunction "2_2") (pintype "passive"))
    )
    (net (code "149") (name "Net-(IC10-B2)") (class "Default")
      (node (ref "IC10") (pin "14") (pinfunction "B2_14") (pintype "output"))
      (node (ref "J11") (pin "1") (pinfunction "1_1") (pintype "passive"))
    )
    (net (code "150") (name "Net-(IC10-I1)") (class "Default")
      (node (ref "IC10") (pin "4") (pinfunction "I1_4") (pintype "passive"))
      (node (ref "SV10") (pin "3") (pinfunction "3_3") (pintype "passive"))
    )
    (net (code "151") (name "Net-(IC10-I2)") (class "Default")
      (node (ref "IC10") (pin "5") (pinfunction "I2_5") (pintype "passive"))
      (node (ref "SV10") (pin "1") (pinfunction "1_1") (pintype "passive"))
    )
    (net (code "152") (name "Net-(IC10-MS1)") (class "Default")
      (node (ref "IC10") (pin "2") (pinfunction "MS1_2") (pintype "passive"))
      (node (ref "SV10") (pin "7") (pinfunction "7_7") (pintype "passive"))
    )
    (net (code "153") (name "Net-(IC10-MS2)") (class "Default")
      (node (ref "IC10") (pin "3") (pinfunction "MS2_3") (pintype "passive"))
      (node (ref "SV10") (pin "5") (pinfunction "5_5") (pintype "passive"))
    )
    (net (code "154") (name "Net-(IC10-~{ENBL})") (class "Default")
      (node (ref "IC10") (pin "1") (pinfunction "~{ENBL}_1") (pintype "passive"))
      (node (ref "SV10") (pin "9") (pinfunction "9_9") (pintype "passive"))
    )
    (net (code "155") (name "Net-(IC11-A1)") (class "Default")
      (node (ref "IC11") (pin "12") (pinfunction "A1_12") (pintype "output"))
      (node (ref "J12") (pin "3") (pinfunction "3_3") (pintype "passive"))
    )
    (net (code "156") (name "Net-(IC11-A2)") (class "Default")
      (node (ref "IC11") (pin "11") (pinfunction "A2_11") (pintype "output"))
      (node (ref "J12") (pin "4") (pinfunction "4_4") (pintype "passive"))
    )
    (net (code "157") (name "Net-(IC11-B1)") (class "Default")
      (node (ref "IC11") (pin "13") (pinfunction "B1_13") (pintype "output"))
      (node (ref "J12") (pin "2") (pinfunction "2_2") (pintype "passive"))
    )
    (net (code "158") (name "Net-(IC11-B2)") (class "Default")
      (node (ref "IC11") (pin "14") (pinfunction "B2_14") (pintype "output"))
      (node (ref "J12") (pin "1") (pinfunction "1_1") (pintype "passive"))
    )
    (net (code "159") (name "Net-(IC11-I1)") (class "Default")
      (node (ref "IC11") (pin "4") (pinfunction "I1_4") (pintype "passive"))
      (node (ref "SV11") (pin "3") (pinfunction "3_3") (pintype "passive"))
    )
    (net (code "160") (name "Net-(IC11-I2)") (class "Default")
      (node (ref "IC11") (pin "5") (pinfunction "I2_5") (pintype "passive"))
      (node (ref "SV11") (pin "1") (pinfunction "1_1") (pintype "passive"))
    )
    (net (code "161") (name "Net-(IC11-MS1)") (class "Default")
      (node (ref "IC11") (pin "2") (pinfunction "MS1_2") (pintype "passive"))
      (node (ref "SV11") (pin "7") (pinfunction "7_7") (pintype "passive"))
    )
    (net (code "162") (name "Net-(IC11-MS2)") (class "Default")
      (node (ref "IC11") (pin "3") (pinfunction "MS2_3") (pintype "passive"))
      (node (ref "SV11") (pin "5") (pinfunction "5_5") (pintype "passive"))
    )
    (net (code "163") (name "Net-(IC11-~{ENBL})") (class "Default")
      (node (ref "IC11") (pin "1") (pinfunction "~{ENBL}_1") (pintype "passive"))
      (node (ref "SV11") (pin "9") (pinfunction "9_9") (pintype "passive"))
    )
    (net (code "164") (name "Net-(IC12-A1)") (class "Default")
      (node (ref "IC12") (pin "12") (pinfunction "A1_12") (pintype "output"))
      (node (ref "J13") (pin "3") (pinfunction "3_3") (pintype "passive"))
    )
    (net (code "165") (name "Net-(IC12-A2)") (class "Default")
      (node (ref "IC12") (pin "11") (pinfunction "A2_11") (pintype "output"))
      (node (ref "J13") (pin "4") (pinfunction "4_4") (pintype "passive"))
    )
    (net (code "166") (name "Net-(IC12-B1)") (class "Default")
      (node (ref "IC12") (pin "13") (pinfunction "B1_13") (pintype "output"))
      (node (ref "J13") (pin "2") (pinfunction "2_2") (pintype "passive"))
    )
    (net (code "167") (name "Net-(IC12-B2)") (class "Default")
      (node (ref "IC12") (pin "14") (pinfunction "B2_14") (pintype "output"))
      (node (ref "J13") (pin "1") (pinfunction "1_1") (pintype "passive"))
    )
    (net (code "168") (name "Net-(IC12-I1)") (class "Default")
      (node (ref "IC12") (pin "4") (pinfunction "I1_4") (pintype "passive"))
      (node (ref "SV12") (pin "3") (pinfunction "3_3") (pintype "passive"))
    )
    (net (code "169") (name "Net-(IC12-I2)") (class "Default")
      (node (ref "IC12") (pin "5") (pinfunction "I2_5") (pintype "passive"))
      (node (ref "SV12") (pin "1") (pinfunction "1_1") (pintype "passive"))
    )
    (net (code "170") (name "Net-(IC12-MS1)") (class "Default")
      (node (ref "IC12") (pin "2") (pinfunction "MS1_2") (pintype "passive"))
      (node (ref "SV12") (pin "7") (pinfunction "7_7") (pintype "passive"))
    )
    (net (code "171") (name "Net-(IC12-MS2)") (class "Default")
      (node (ref "IC12") (pin "3") (pinfunction "MS2_3") (pintype "passive"))
      (node (ref "SV12") (pin "5") (pinfunction "5_5") (pintype "passive"))
    )
    (net (code "172") (name "Net-(IC12-~{ENBL})") (class "Default")
      (node (ref "IC12") (pin "1") (pinfunction "~{ENBL}_1") (pintype "passive"))
      (node (ref "SV12") (pin "9") (pinfunction "9_9") (pintype "passive"))
    )
    (net (code "173") (name "Net-(IC13-A1)") (class "Default")
      (node (ref "IC13") (pin "12") (pinfunction "A1_12") (pintype "output"))
      (node (ref "J14") (pin "3") (pinfunction "3_3") (pintype "passive"))
    )
    (net (code "174") (name "Net-(IC13-A2)") (class "Default")
      (node (ref "IC13") (pin "11") (pinfunction "A2_11") (pintype "output"))
      (node (ref "J14") (pin "4") (pinfunction "4_4") (pintype "passive"))
    )
    (net (code "175") (name "Net-(IC13-B1)") (class "Default")
      (node (ref "IC13") (pin "13") (pinfunction "B1_13") (pintype "output"))
      (node (ref "J14") (pin "2") (pinfunction "2_2") (pintype "passive"))
    )
    (net (code "176") (name "Net-(IC13-B2)") (class "Default")
      (node (ref "IC13") (pin "14") (pinfunction "B2_14") (pintype "output"))
      (node (ref "J14") (pin "1") (pinfunction "1_1") (pintype "passive"))
    )
    (net (code "177") (name "Net-(IC13-I1)") (class "Default")
      (node (ref "IC13") (pin "4") (pinfunction "I1_4") (pintype "passive"))
      (node (ref "SV13") (pin "3") (pinfunction "3_3") (pintype "passive"))
    )
    (net (code "178") (name "Net-(IC13-I2)") (class "Default")
      (node (ref "IC13") (pin "5") (pinfunction "I2_5") (pintype "passive"))
      (node (ref "SV13") (pin "1") (pinfunction "1_1") (pintype "passive"))
    )
    (net (code "179") (name "Net-(IC13-MS1)") (class "Default")
      (node (ref "IC13") (pin "2") (pinfunction "MS1_2") (pintype "passive"))
      (node (ref "SV13") (pin "7") (pinfunction "7_7") (pintype "passive"))
    )
    (net (code "180") (name "Net-(IC13-MS2)") (class "Default")
      (node (ref "IC13") (pin "3") (pinfunction "MS2_3") (pintype "passive"))
      (node (ref "SV13") (pin "5") (pinfunction "5_5") (pintype "passive"))
    )
    (net (code "181") (name "Net-(IC13-~{ENBL})") (class "Default")
      (node (ref "IC13") (pin "1") (pinfunction "~{ENBL}_1") (pintype "passive"))
      (node (ref "SV13") (pin "9") (pinfunction "9_9") (pintype "passive"))
    )
    (net (code "182") (name "Net-(IC14-A1)") (class "Default")
      (node (ref "IC14") (pin "12") (pinfunction "A1_12") (pintype "output"))
      (node (ref "J15") (pin "3") (pinfunction "3_3") (pintype "passive"))
    )
    (net (code "183") (name "Net-(IC14-A2)") (class "Default")
      (node (ref "IC14") (pin "11") (pinfunction "A2_11") (pintype "output"))
      (node (ref "J15") (pin "4") (pinfunction "4_4") (pintype "passive"))
    )
    (net (code "184") (name "Net-(IC14-B1)") (class "Default")
      (node (ref "IC14") (pin "13") (pinfunction "B1_13") (pintype "output"))
      (node (ref "J15") (pin "2") (pinfunction "2_2") (pintype "passive"))
    )
    (net (code "185") (name "Net-(IC14-B2)") (class "Default")
      (node (ref "IC14") (pin "14") (pinfunction "B2_14") (pintype "output"))
      (node (ref "J15") (pin "1") (pinfunction "1_1") (pintype "passive"))
    )
    (net (code "186") (name "Net-(IC14-I1)") (class "Default")
      (node (ref "IC14") (pin "4") (pinfunction "I1_4") (pintype "passive"))
      (node (ref "SV14") (pin "3") (pinfunction "3_3") (pintype "passive"))
    )
    (net (code "187") (name "Net-(IC14-I2)") (class "Default")
      (node (ref "IC14") (pin "5") (pinfunction "I2_5") (pintype "passive"))
      (node (ref "SV14") (pin "1") (pinfunction "1_1") (pintype "passive"))
    )
    (net (code "188") (name "Net-(IC14-MS1)") (class "Default")
      (node (ref "IC14") (pin "2") (pinfunction "MS1_2") (pintype "passive"))
      (node (ref "SV14") (pin "7") (pinfunction "7_7") (pintype "passive"))
    )
    (net (code "189") (name "Net-(IC14-MS2)") (class "Default")
      (node (ref "IC14") (pin "3") (pinfunction "MS2_3") (pintype "passive"))
      (node (ref "SV14") (pin "5") (pinfunction "5_5") (pintype "passive"))
    )
    (net (code "190") (name "Net-(IC14-~{ENBL})") (class "Default")
      (node (ref "IC14") (pin "1") (pinfunction "~{ENBL}_1") (pintype "passive"))
      (node (ref "SV14") (pin "9") (pinfunction "9_9") (pintype "passive"))
    )
    (net (code "191") (name "Net-(IC15-A1)") (class "Default")
      (node (ref "IC15") (pin "12") (pinfunction "A1_12") (pintype "output"))
      (node (ref "J16") (pin "3") (pinfunction "3_3") (pintype "passive"))
    )
    (net (code "192") (name "Net-(IC15-A2)") (class "Default")
      (node (ref "IC15") (pin "11") (pinfunction "A2_11") (pintype "output"))
      (node (ref "J16") (pin "4") (pinfunction "4_4") (pintype "passive"))
    )
    (net (code "193") (name "Net-(IC15-B1)") (class "Default")
      (node (ref "IC15") (pin "13") (pinfunction "B1_13") (pintype "output"))
      (node (ref "J16") (pin "2") (pinfunction "2_2") (pintype "passive"))
    )
    (net (code "194") (name "Net-(IC15-B2)") (class "Default")
      (node (ref "IC15") (pin "14") (pinfunction "B2_14") (pintype "output"))
      (node (ref "J16") (pin "1") (pinfunction "1_1") (pintype "passive"))
    )
    (net (code "195") (name "Net-(IC15-I1)") (class "Default")
      (node (ref "IC15") (pin "4") (pinfunction "I1_4") (pintype "passive"))
      (node (ref "SV15") (pin "3") (pinfunction "3_3") (pintype "passive"))
    )
    (net (code "196") (name "Net-(IC15-I2)") (class "Default")
      (node (ref "IC15") (pin "5") (pinfunction "I2_5") (pintype "passive"))
      (node (ref "SV15") (pin "1") (pinfunction "1_1") (pintype "passive"))
    )
    (net (code "197") (name "Net-(IC15-MS1)") (class "Default")
      (node (ref "IC15") (pin "2") (pinfunction "MS1_2") (pintype "passive"))
      (node (ref "SV15") (pin "7") (pinfunction "7_7") (pintype "passive"))
    )
    (net (code "198") (name "Net-(IC15-MS2)") (class "Default")
      (node (ref "IC15") (pin "3") (pinfunction "MS2_3") (pintype "passive"))
      (node (ref "SV15") (pin "5") (pinfunction "5_5") (pintype "passive"))
    )
    (net (code "199") (name "Net-(IC15-~{ENBL})") (class "Default")
      (node (ref "IC15") (pin "1") (pinfunction "~{ENBL}_1") (pintype "passive"))
      (node (ref "SV15") (pin "9") (pinfunction "9_9") (pintype "passive"))
    )
    (net (code "200") (name "unconnected-(IC1-~{FLT}-Pad10)") (class "Default")
      (node (ref "IC1") (pin "10") (pinfunction "~{FLT}_10") (pintype "open_collector"))
    )
    (net (code "201") (name "unconnected-(IC2-~{FLT}-Pad10)") (class "Default")
      (node (ref "IC2") (pin "10") (pinfunction "~{FLT}_10") (pintype "open_collector"))
    )
    (net (code "202") (name "unconnected-(IC3-~{FLT}-Pad10)") (class "Default")
      (node (ref "IC3") (pin "10") (pinfunction "~{FLT}_10") (pintype "open_collector"))
    )
    (net (code "203") (name "unconnected-(IC4-~{FLT}-Pad10)") (class "Default")
      (node (ref "IC4") (pin "10") (pinfunction "~{FLT}_10") (pintype "open_collector"))
    )
    (net (code "204") (name "unconnected-(IC5-~{FLT}-Pad10)") (class "Default")
      (node (ref "IC5") (pin "10") (pinfunction "~{FLT}_10") (pintype "open_collector"))
    )
    (net (code "205") (name "unconnected-(IC6-~{FLT}-Pad10)") (class "Default")
      (node (ref "IC6") (pin "10") (pinfunction "~{FLT}_10") (pintype "open_collector"))
    )
    (net (code "206") (name "unconnected-(IC7-~{FLT}-Pad10)") (class "Default")
      (node (ref "IC7") (pin "10") (pinfunction "~{FLT}_10") (pintype "open_collector"))
    )
    (net (code "207") (name "unconnected-(IC8-~{FLT}-Pad10)") (class "Default")
      (node (ref "IC8") (pin "10") (pinfunction "~{FLT}_10") (pintype "open_collector"))
    )
    (net (code "208") (name "unconnected-(IC9-~{FLT}-Pad10)") (class "Default")
      (node (ref "IC9") (pin "10") (pinfunction "~{FLT}_10") (pintype "open_collector"))
    )
    (net (code "209") (name "unconnected-(IC10-~{FLT}-Pad10)") (class "Default")
      (node (ref "IC10") (pin "10") (pinfunction "~{FLT}_10") (pintype "open_collector"))
    )
    (net (code "210") (name "unconnected-(IC11-~{FLT}-Pad10)") (class "Default")
      (node (ref "IC11") (pin "10") (pinfunction "~{FLT}_10") (pintype "open_collector"))
    )
    (net (code "211") (name "unconnected-(IC12-~{FLT}-Pad10)") (class "Default")
      (node (ref "IC12") (pin "10") (pinfunction "~{FLT}_10") (pintype "open_collector"))
    )
    (net (code "212") (name "unconnected-(IC13-~{FLT}-Pad10)") (class "Default")
      (node (ref "IC13") (pin "10") (pinfunction "~{FLT}_10") (pintype "open_collector"))
    )
    (net (code "213") (name "unconnected-(IC14-~{FLT}-Pad10)") (class "Default")
      (node (ref "IC14") (pin "10") (pinfunction "~{FLT}_10") (pintype "open_collector"))
    )
    (net (code "214") (name "unconnected-(IC15-~{FLT}-Pad10)") (class "Default")
      (node (ref "IC15") (pin "10") (pinfunction "~{FLT}_10") (pintype "open_collector"))
    )
    (net (code "215") (name "unconnected-(JP1-Pad1)") (class "Default")
      (node (ref "JP1") (pin "1") (pinfunction "1_1") (pintype "passive"))
    )
    (net (code "216") (name "unconnected-(JP1-Pad2)") (class "Default")
      (node (ref "JP1") (pin "2") (pinfunction "2_2") (pintype "passive"))
    )
    (net (code "217") (name "unconnected-(JP1-Pad3)") (class "Default")
      (node (ref "JP1") (pin "3") (pinfunction "3_3") (pintype "passive"))
    )
    (net (code "218") (name "unconnected-(JP1-Pad4)") (class "Default")
      (node (ref "JP1") (pin "4") (pinfunction "4_4") (pintype "passive"))
    )
    (net (code "219") (name "unconnected-(JP1-Pad5)") (class "Default")
      (node (ref "JP1") (pin "5") (pinfunction "5_5") (pintype "passive"))
    )
    (net (code "220") (name "unconnected-(JP1-Pad6)") (class "Default")
      (node (ref "JP1") (pin "6") (pinfunction "6_6") (pintype "passive"))
    )
    (net (code "221") (name "unconnected-(JP1-Pad7)") (class "Default")
      (node (ref "JP1") (pin "7") (pinfunction "7_7") (pintype "passive"))
    )
    (net (code "222") (name "unconnected-(JP1-Pad8)") (class "Default")
      (node (ref "JP1") (pin "8") (pinfunction "8_8") (pintype "passive"))
    )
    (net (code "223") (name "unconnected-(JP2-Pad1)") (class "Default")
      (node (ref "JP2") (pin "1") (pinfunction "1_1") (pintype "passive"))
    )
    (net (code "224") (name "unconnected-(JP2-Pad2)") (class "Default")
      (node (ref "JP2") (pin "2") (pinfunction "2_2") (pintype "passive"))
    )
    (net (code "225") (name "unconnected-(JP2-Pad33)") (class "Default")
      (node (ref "JP2") (pin "33") (pinfunction "33_33") (pintype "passive"))
    )
    (net (code "226") (name "unconnected-(JP2-Pad34)") (class "Default")
      (node (ref "JP2") (pin "34") (pinfunction "34_34") (pintype "passive"))
    )
    (net (code "227") (name "unconnected-(JP2-Pad35)") (class "Default")
      (node (ref "JP2") (pin "35") (pinfunction "35_35") (pintype "passive"))
    )
    (net (code "228") (name "unconnected-(JP2-Pad36)") (class "Default")
      (node (ref "JP2") (pin "36") (pinfunction "36_36") (pintype "passive"))
    )
    (net (code "229") (name "unconnected-(JP4-Pad1)") (class "Default")
      (node (ref "JP4") (pin "1") (pinfunction "1_1") (pintype "passive"))
    )
  )
)
